# Logger.net
KiCad netlist of a schematic drawn in EAGLE
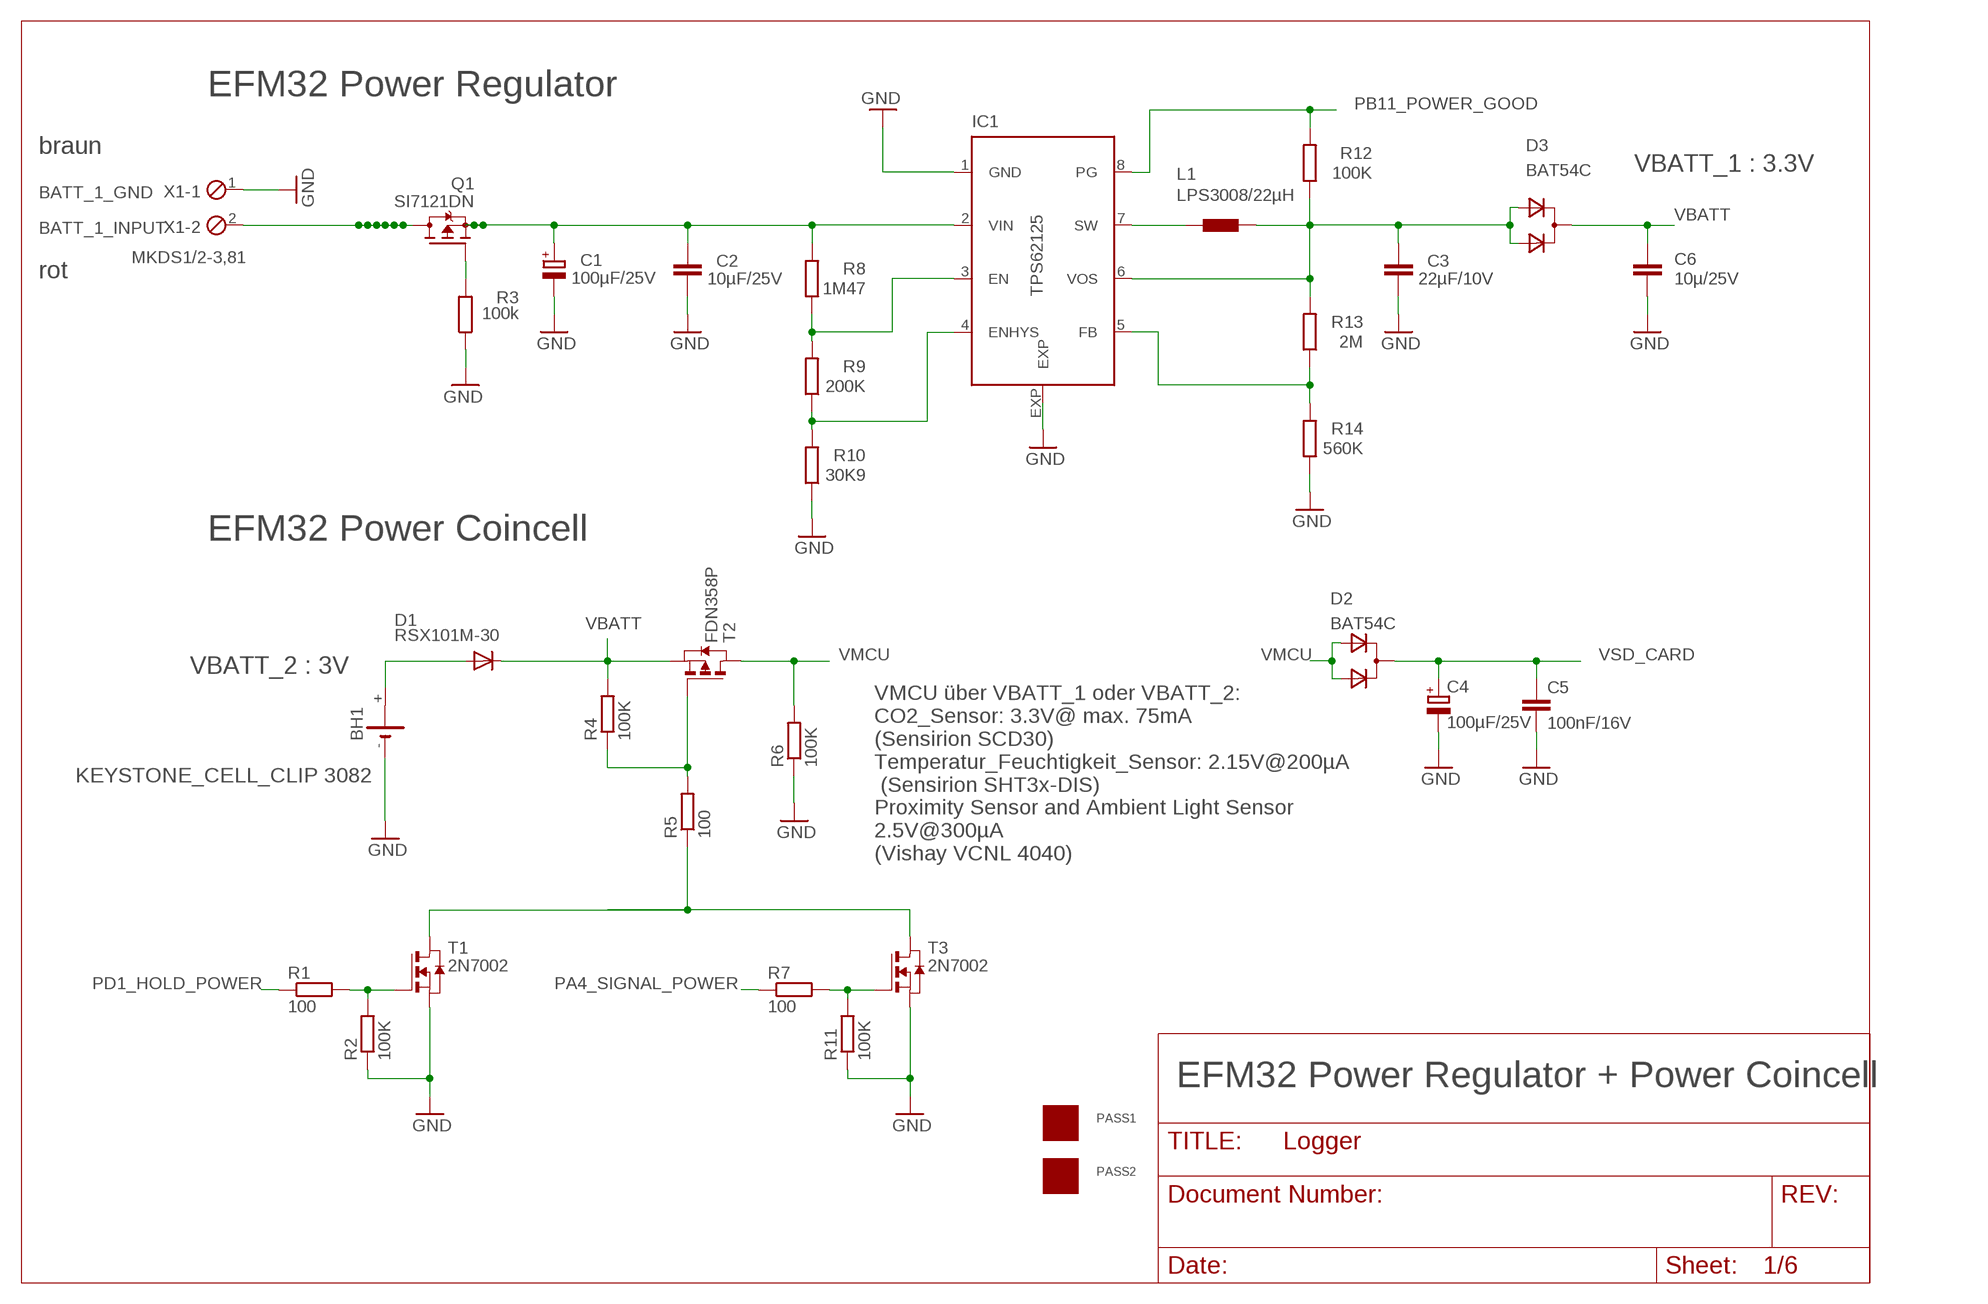
[diagram p0: schematic, sheet 1]
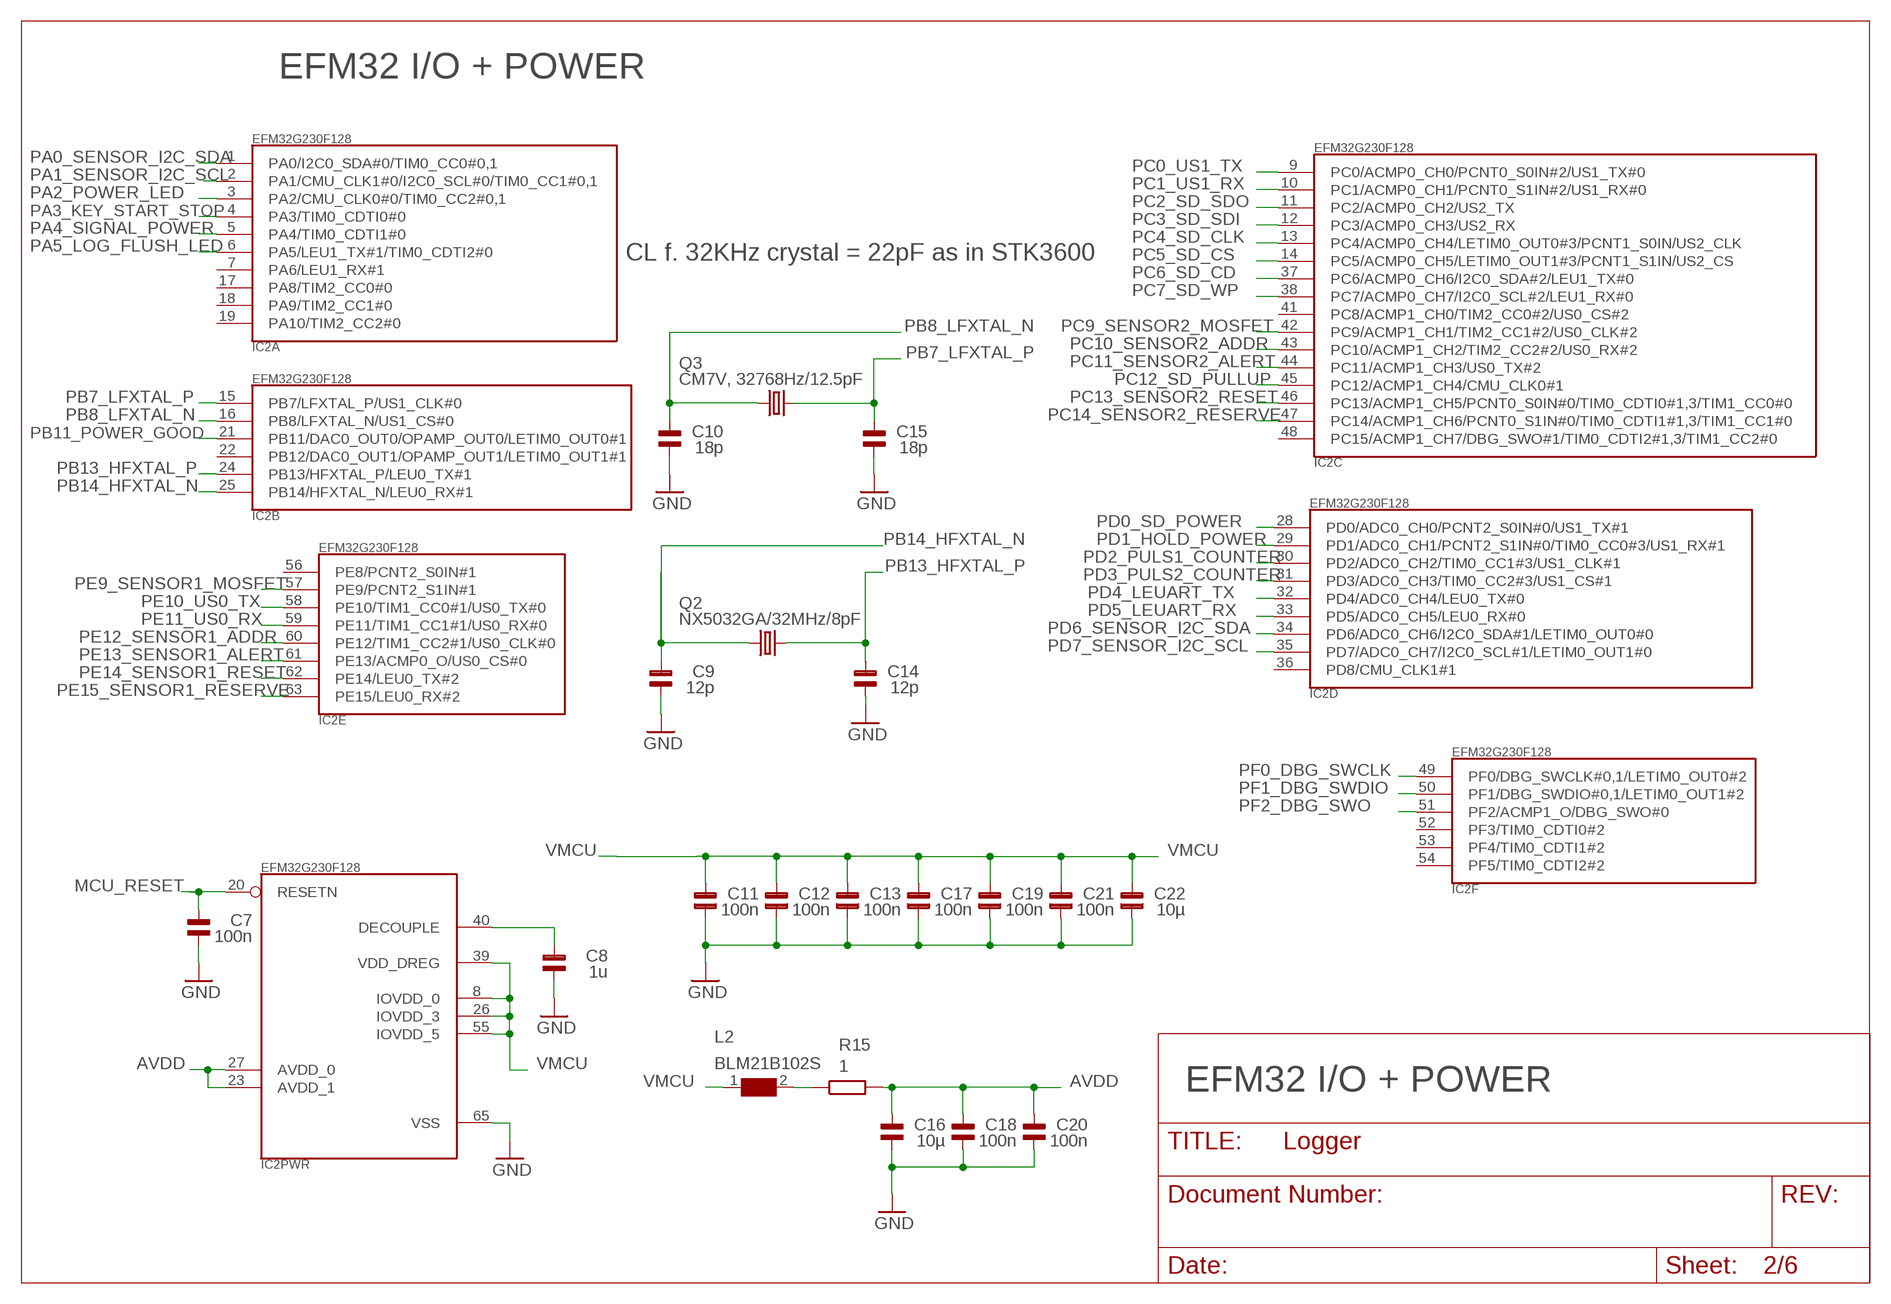
[diagram p1: schematic, sheet 2]
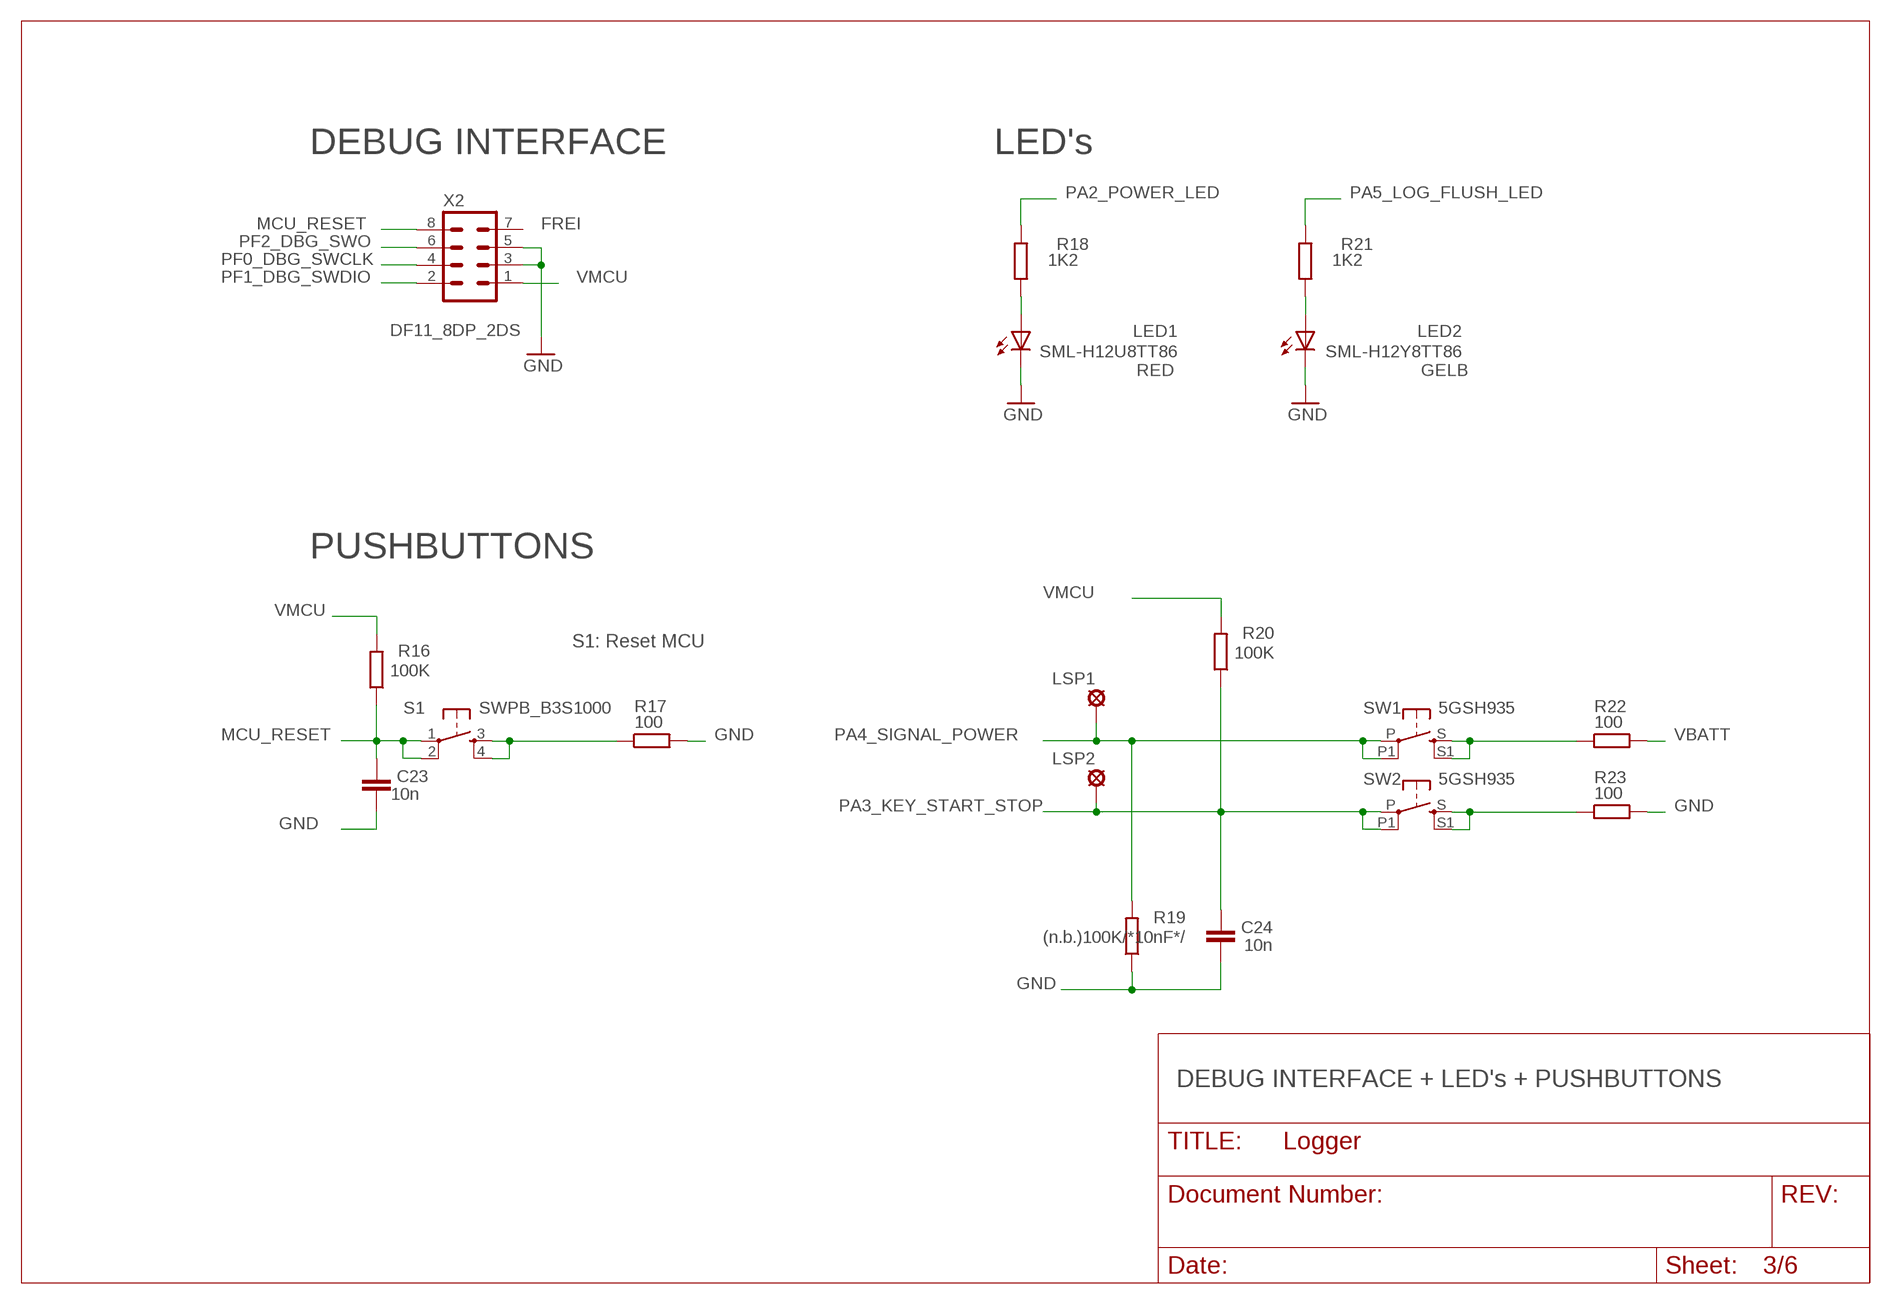
[diagram p2: schematic, sheet 3]
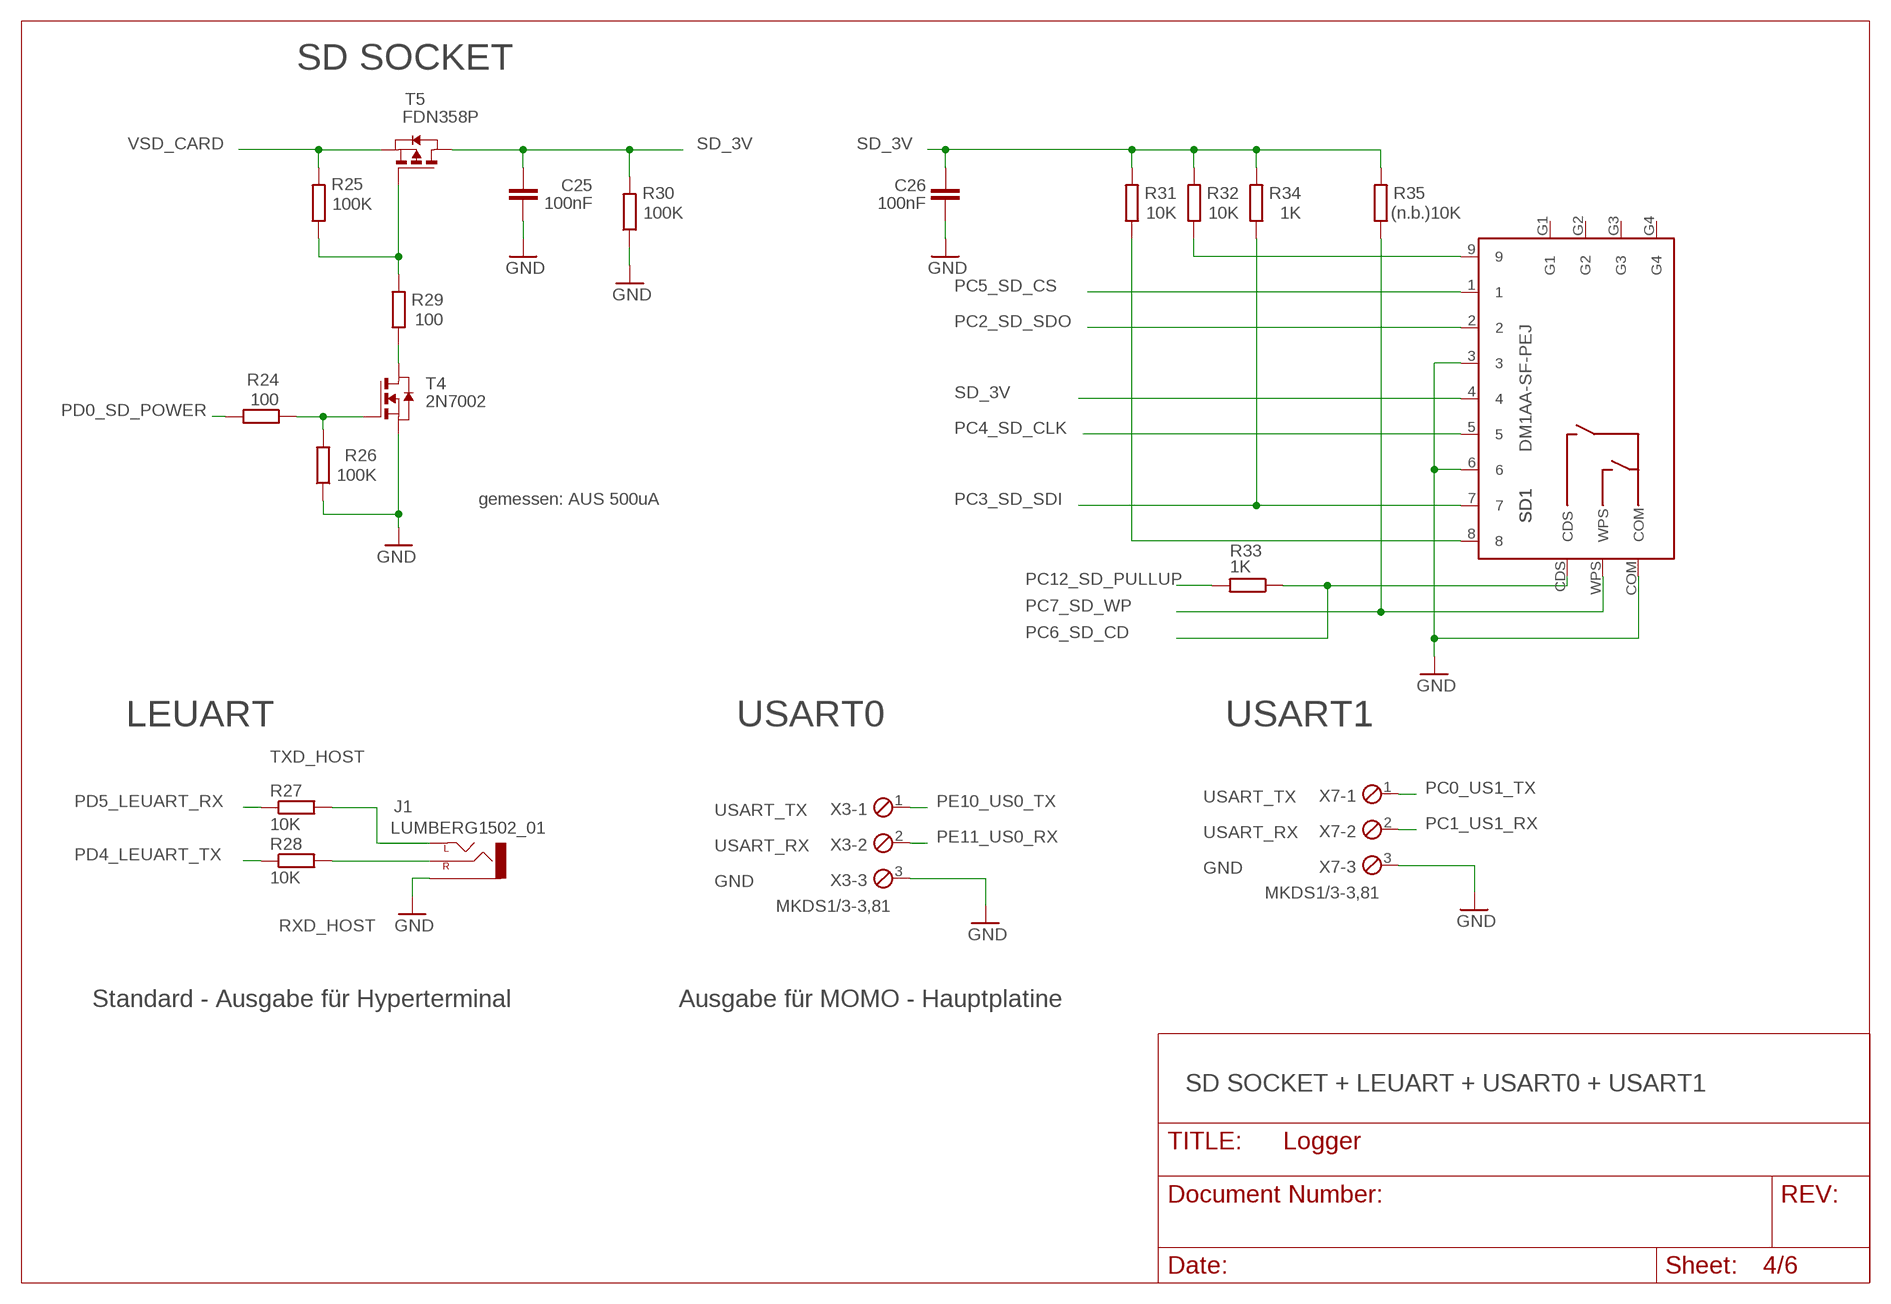
[diagram p3: schematic, sheet 4]
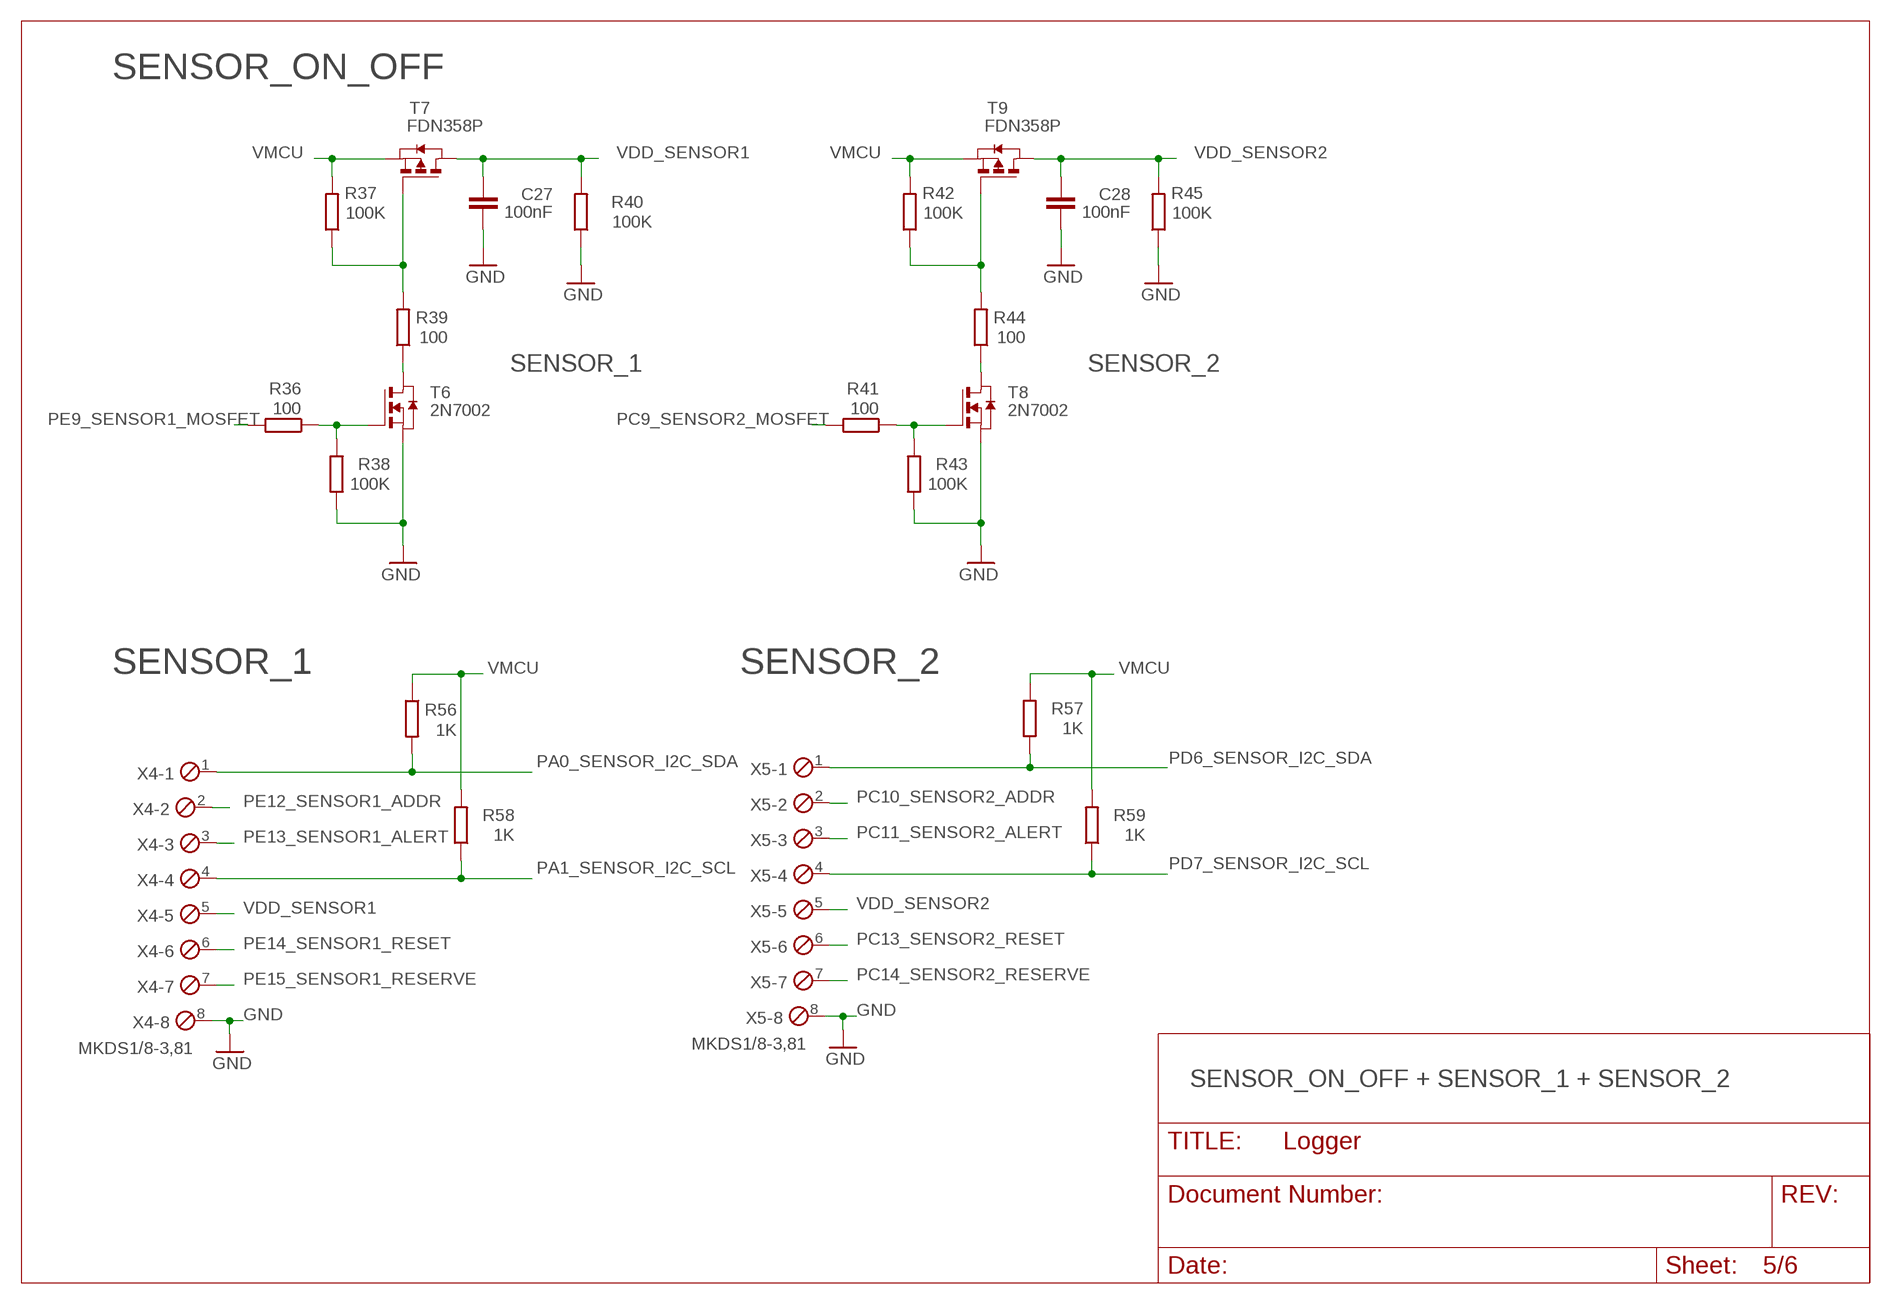
[diagram p4: schematic, sheet 5]
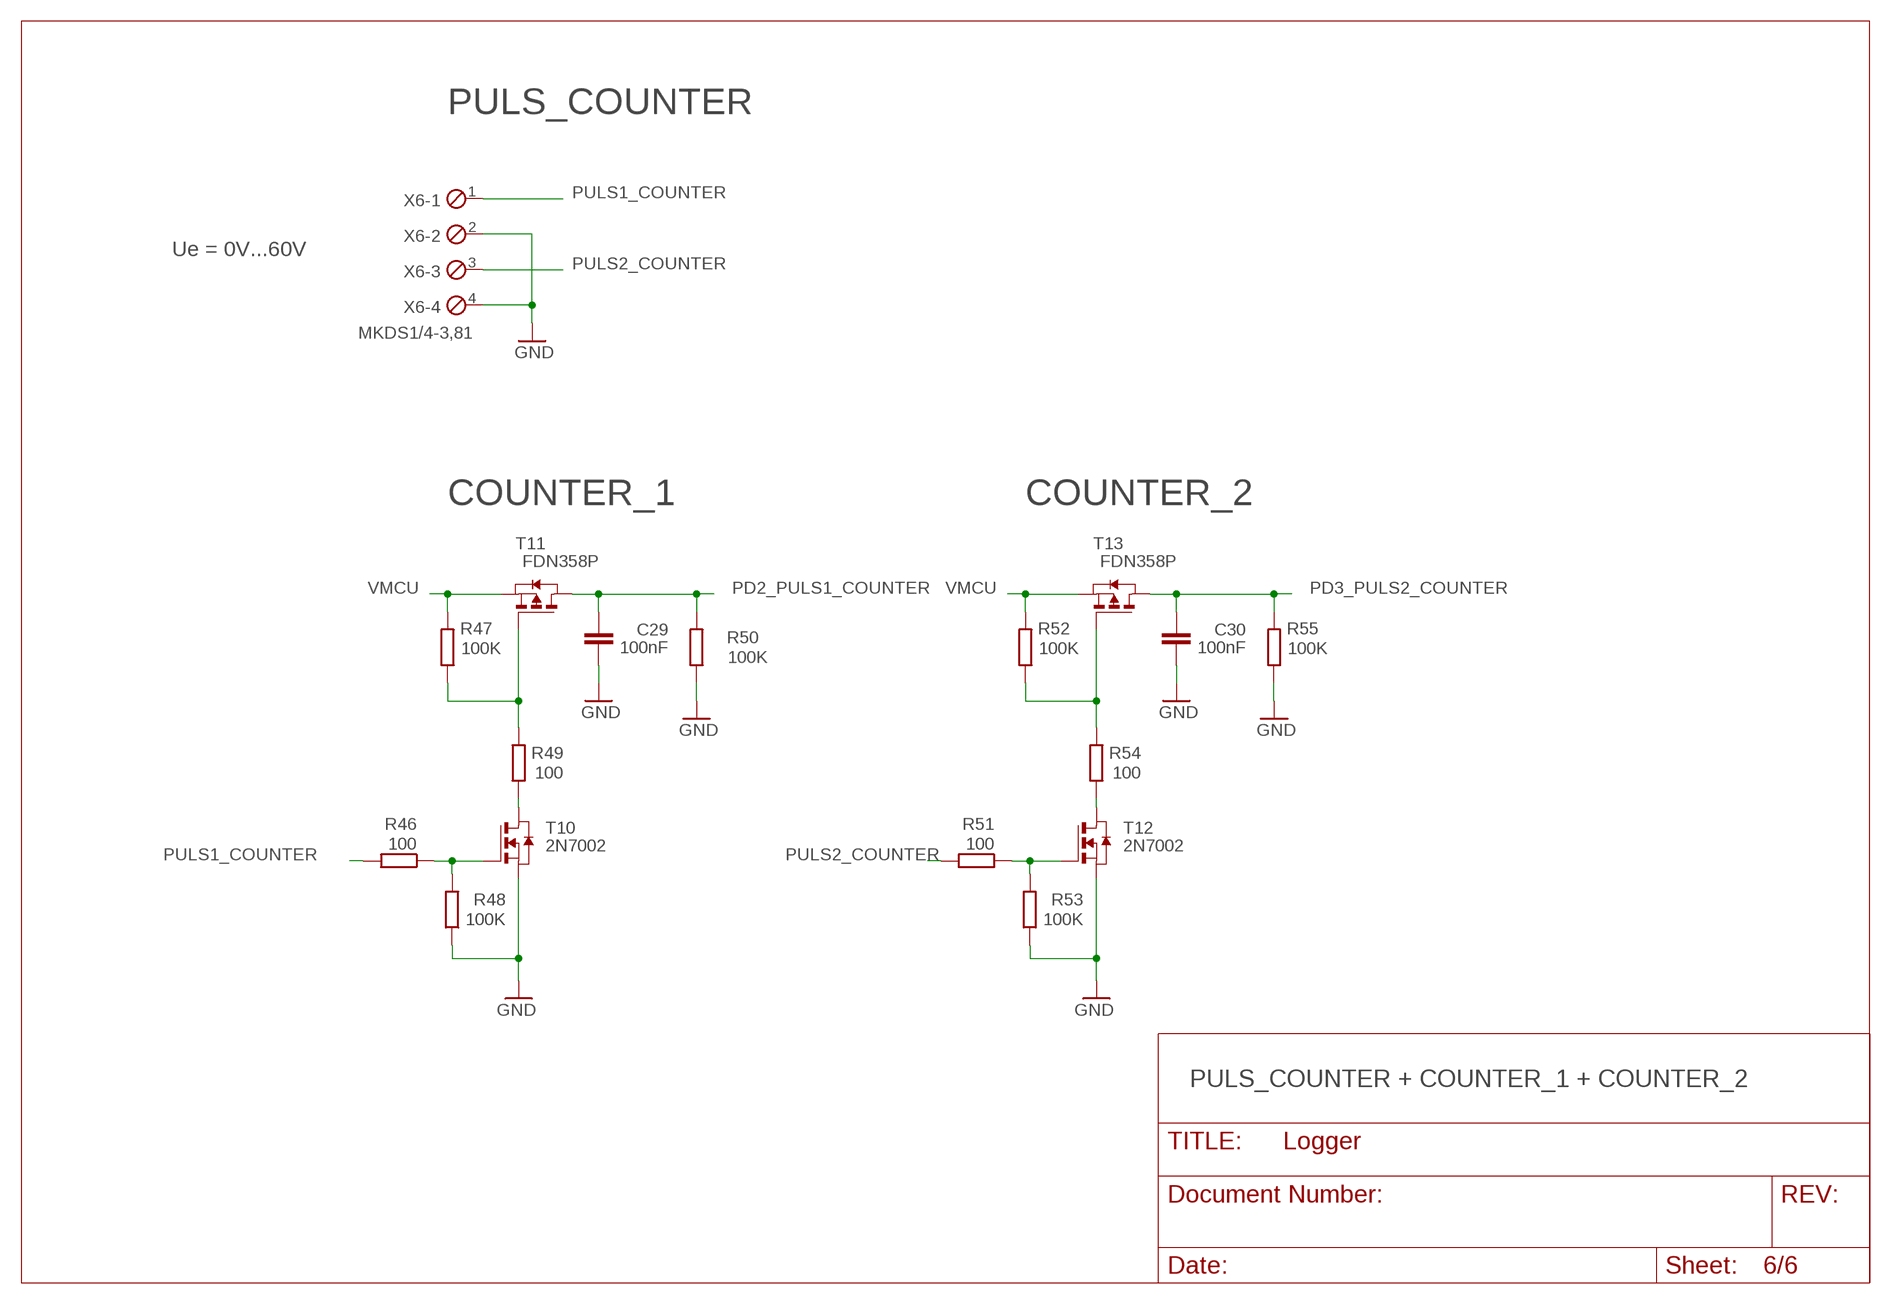
[diagram p5: schematic, sheet 6]

(export (version "E")
  (design (tool "Eeschema 10.0.6"))
  (components
    (comp (ref "C25")
      (value "100nF")
      (footprint "eagle-import:C0603")
      (libsource (lib "eagle-import") (part "resistor_C-EUC0603"))
    )
    (comp (ref "C26")
      (value "100nF")
      (footprint "eagle-import:C0603")
      (libsource (lib "eagle-import") (part "resistor_C-EUC0603"))
    )
    (comp (ref "J1")
      (value "LUMBERG1502_01")
      (footprint "eagle-import:LUMBERG1502_01")
      (libsource (lib "eagle-import") (part "LUMBERG1502_01"))
    )
    (comp (ref "R24")
      (value "100")
      (footprint "eagle-import:R0805")
      (libsource (lib "eagle-import") (part "resistor_R-EU_R0805"))
    )
    (comp (ref "R25")
      (value "100K")
      (footprint "eagle-import:R0805")
      (libsource (lib "eagle-import") (part "resistor_R-EU_R0805"))
    )
    (comp (ref "R26")
      (value "100K")
      (footprint "eagle-import:R0805")
      (libsource (lib "eagle-import") (part "resistor_R-EU_R0805"))
    )
    (comp (ref "R27")
      (value "10K")
      (footprint "eagle-import:R0805")
      (libsource (lib "eagle-import") (part "R-EU_R0805"))
    )
    (comp (ref "R28")
      (value "10K")
      (footprint "eagle-import:R0805")
      (libsource (lib "eagle-import") (part "R-EU_R0805"))
    )
    (comp (ref "R29")
      (value "100")
      (footprint "eagle-import:R0805")
      (libsource (lib "eagle-import") (part "resistor_R-EU_R0805"))
    )
    (comp (ref "R30")
      (value "100K")
      (footprint "eagle-import:R0805")
      (libsource (lib "eagle-import") (part "resistor_R-EU_R0805"))
    )
    (comp (ref "R31")
      (value "10K")
      (footprint "eagle-import:R0805")
      (libsource (lib "eagle-import") (part "resistor_R-EU_R0805"))
    )
    (comp (ref "R32")
      (value "10K")
      (footprint "eagle-import:R0805")
      (libsource (lib "eagle-import") (part "resistor_R-EU_R0805"))
    )
    (comp (ref "R33")
      (value "1K")
      (footprint "eagle-import:R0805")
      (libsource (lib "eagle-import") (part "resistor_R-EU_R0805"))
    )
    (comp (ref "R34")
      (value "1K")
      (footprint "eagle-import:R0805")
      (libsource (lib "eagle-import") (part "resistor_R-EU_R0805"))
    )
    (comp (ref "R35")
      (value "(n.b.)10K")
      (footprint "eagle-import:R0805")
      (libsource (lib "eagle-import") (part "resistor_R-EU_R0805"))
    )
    (comp (ref "SD1")
      (value "DM1AA-SF-PEJ")
      (footprint "eagle-import:DM1AA-SF-PEJ")
      (libsource (lib "eagle-import") (part "DM1AA-SF-PEJ"))
    )
    (comp (ref "T4")
      (value "2N7002")
      (footprint "eagle-import:ZETEX_SOT-23")
      (libsource (lib "eagle-import") (part "ZETEX_NMOSSOT23"))
    )
    (comp (ref "T5")
      (value "FDN358P")
      (footprint "eagle-import:ZETEX_SOT-23")
      (libsource (lib "eagle-import") (part "ZETEX_PMOSSOT23"))
    )
    (comp (ref "X3")
      (value "MKDS1/3-3,81")
      (footprint "eagle-import:3POL381")
      (libsource (lib "eagle-import") (part "MKDS1/3-3,81"))
    )
    (comp (ref "X7")
      (value "MKDS1/3-3,81")
      (footprint "eagle-import:3POL381")
      (libsource (lib "eagle-import") (part "MKDS1/3-3,81"))
    )
    (comp (ref "BH1")
      (value "KEYSTONE_CELL_CLIP 3082")
      (footprint "eagle-import:3082")
      (libsource (lib "eagle-import") (part "3082"))
    )
    (comp (ref "C1")
      (value "100µF/25V")
      (footprint "eagle-import:PANASONIC_E")
      (libsource (lib "eagle-import") (part "CPOL-EUE"))
    )
    (comp (ref "C2")
      (value "10µF/25V")
      (footprint "eagle-import:C1206")
      (libsource (lib "eagle-import") (part "C-EUC1206"))
    )
    (comp (ref "C3")
      (value "22µF/10V")
      (footprint "eagle-import:C0603")
      (libsource (lib "eagle-import") (part "C-EUC0603"))
    )
    (comp (ref "C4")
      (value "100µF/25V")
      (footprint "eagle-import:PANASONIC_E")
      (libsource (lib "eagle-import") (part "CPOL-EUE"))
    )
    (comp (ref "C5")
      (value "100nF/16V")
      (footprint "eagle-import:C0805")
      (libsource (lib "eagle-import") (part "C-EUC0805"))
    )
    (comp (ref "C6")
      (value "10µ/25V")
      (footprint "eagle-import:C1206")
      (libsource (lib "eagle-import") (part "C-EUC1206"))
    )
    (comp (ref "D1")
      (value "RSX101M-30")
      (footprint "eagle-import:SOD123")
      (libsource (lib "eagle-import") (part "DIODE-SOD123"))
    )
    (comp (ref "D2")
      (value "BAT54C")
      (footprint "eagle-import:SOT-23$1")
      (libsource (lib "eagle-import") (part "D2A_SOT23"))
    )
    (comp (ref "D3")
      (value "BAT54C")
      (footprint "eagle-import:SOT-23$1")
      (libsource (lib "eagle-import") (part "D2A_SOT23"))
    )
    (comp (ref "IC1")
      (value "TPS62125")
      (footprint "eagle-import:DSG_PWSO-N8_EXP")
      (libsource (lib "eagle-import") (part "TPS62125"))
    )
    (comp (ref "L1")
      (value "LPS3008/22µH")
      (footprint "eagle-import:LPS3008")
      (libsource (lib "eagle-import") (part "LPS3008"))
    )
    (comp (ref "PASS1")
      (value "ROUND_1MM1.5")
      (footprint "eagle-import:ROUND2_1.5MM")
      (libsource (lib "eagle-import") (part "ROUND_1MM1.5"))
    )
    (comp (ref "PASS2")
      (value "ROUND_1MM1.5")
      (footprint "eagle-import:ROUND2_1.5MM")
      (libsource (lib "eagle-import") (part "ROUND_1MM1.5"))
    )
    (comp (ref "Q1")
      (value "SI7121DN")
      (footprint "eagle-import:TRANSISTOR-FET_1212-8S")
      (libsource (lib "eagle-import") (part "TRANSISTOR-FET_SI7113DN"))
    )
    (comp (ref "R1")
      (value "100")
      (footprint "eagle-import:R0805")
      (libsource (lib "eagle-import") (part "R-EU_R0805"))
    )
    (comp (ref "R2")
      (value "100K")
      (footprint "eagle-import:R0805")
      (libsource (lib "eagle-import") (part "R-EU_R0805"))
    )
    (comp (ref "R3")
      (value "100k")
      (footprint "eagle-import:R0805")
      (libsource (lib "eagle-import") (part "resistor_R-EU_R0805"))
    )
    (comp (ref "R4")
      (value "100K")
      (footprint "eagle-import:R0805")
      (libsource (lib "eagle-import") (part "R-EU_R0805"))
    )
    (comp (ref "R5")
      (value "100")
      (footprint "eagle-import:R0805")
      (libsource (lib "eagle-import") (part "R-EU_R0805"))
    )
    (comp (ref "R6")
      (value "100K")
      (footprint "eagle-import:R0805")
      (libsource (lib "eagle-import") (part "R-EU_R0805"))
    )
    (comp (ref "R7")
      (value "100")
      (footprint "eagle-import:R0805")
      (libsource (lib "eagle-import") (part "R-EU_R0805"))
    )
    (comp (ref "R8")
      (value "1M47")
      (footprint "eagle-import:R0805")
      (libsource (lib "eagle-import") (part "R-EU_R0805"))
    )
    (comp (ref "R9")
      (value "200K")
      (footprint "eagle-import:R0805")
      (libsource (lib "eagle-import") (part "R-EU_R0805"))
    )
    (comp (ref "R10")
      (value "30K9")
      (footprint "eagle-import:R0805")
      (libsource (lib "eagle-import") (part "R-EU_R0805"))
    )
    (comp (ref "R11")
      (value "100K")
      (footprint "eagle-import:R0805")
      (libsource (lib "eagle-import") (part "R-EU_R0805"))
    )
    (comp (ref "R12")
      (value "100K")
      (footprint "eagle-import:R0805")
      (libsource (lib "eagle-import") (part "R-EU_R0805"))
    )
    (comp (ref "R13")
      (value "2M")
      (footprint "eagle-import:R0805")
      (libsource (lib "eagle-import") (part "R-EU_R0805"))
    )
    (comp (ref "R14")
      (value "560K")
      (footprint "eagle-import:R0805")
      (libsource (lib "eagle-import") (part "R-EU_R0805"))
    )
    (comp (ref "T1")
      (value "2N7002")
      (footprint "eagle-import:SOT-23")
      (fields (field (name "OC_FARNELL") "unknown") (field (name "OC_NEWARK") "unknown"))
      (libsource (lib "eagle-import") (part "NMOSSOT23"))
    )
    (comp (ref "T2")
      (value "FDN358P")
      (footprint "eagle-import:ZETEX_SOT-23")
      (libsource (lib "eagle-import") (part "ZETEX_PMOSSOT23"))
    )
    (comp (ref "T3")
      (value "2N7002")
      (footprint "eagle-import:SOT-23")
      (fields (field (name "OC_FARNELL") "unknown") (field (name "OC_NEWARK") "unknown"))
      (libsource (lib "eagle-import") (part "NMOSSOT23"))
    )
    (comp (ref "X1")
      (value "MKDS1/2-3,81")
      (footprint "eagle-import:2POL381")
      (libsource (lib "eagle-import") (part "MKDS1/2-3,81"))
    )
    (comp (ref "C23")
      (value "10n")
      (footprint "eagle-import:C0603")
      (libsource (lib "eagle-import") (part "resistor_C-EUC0603"))
    )
    (comp (ref "C24")
      (value "10n")
      (footprint "eagle-import:C0603K")
      (libsource (lib "eagle-import") (part "C-EUC0603K"))
    )
    (comp (ref "LED1")
      (value "SML-H12U8TT86")
      (footprint "eagle-import:CHIPLED_0805")
      (libsource (lib "eagle-import") (part "LEDCHIPLED_0805"))
    )
    (comp (ref "LED2")
      (value "SML-H12Y8TT86")
      (footprint "eagle-import:CHIPLED_0805")
      (libsource (lib "eagle-import") (part "LEDCHIPLED_0805"))
    )
    (comp (ref "LSP1")
      (value "(n.b.)SE13")
      (footprint "eagle-import:SE13")
      (libsource (lib "eagle-import") (part "SE13"))
    )
    (comp (ref "LSP2")
      (value "(n.b.)SE13")
      (footprint "eagle-import:SE13")
      (libsource (lib "eagle-import") (part "SE13"))
    )
    (comp (ref "R16")
      (value "100K")
      (footprint "eagle-import:R0805")
      (libsource (lib "eagle-import") (part "resistor_R-EU_R0805"))
    )
    (comp (ref "R17")
      (value "100")
      (footprint "eagle-import:R0805")
      (libsource (lib "eagle-import") (part "resistor_R-EU_R0805"))
    )
    (comp (ref "R18")
      (value "1K2")
      (footprint "eagle-import:R0805")
      (libsource (lib "eagle-import") (part "resistor_R-EU_R0805"))
    )
    (comp (ref "R19")
      (value "(n.b.)100K/*10nF*/")
      (footprint "eagle-import:R0805")
      (libsource (lib "eagle-import") (part "resistor_R-EU_R0805"))
    )
    (comp (ref "R20")
      (value "100K")
      (footprint "eagle-import:R0805")
      (libsource (lib "eagle-import") (part "resistor_R-EU_R0805"))
    )
    (comp (ref "R21")
      (value "1K2")
      (footprint "eagle-import:R0805")
      (libsource (lib "eagle-import") (part "resistor_R-EU_R0805"))
    )
    (comp (ref "R22")
      (value "100")
      (footprint "eagle-import:R0805")
      (libsource (lib "eagle-import") (part "resistor_R-EU_R0805"))
    )
    (comp (ref "R23")
      (value "100")
      (footprint "eagle-import:R0805")
      (libsource (lib "eagle-import") (part "resistor_R-EU_R0805"))
    )
    (comp (ref "S1")
      (value "SWPB_B3S1000")
      (footprint "eagle-import:DTSM-6")
      (libsource (lib "eagle-import") (part "DTSM-6"))
    )
    (comp (ref "SW1")
      (value "5GSH935")
      (footprint "eagle-import:MULTIMEC_5GSH935")
      (libsource (lib "eagle-import") (part "5GSH935"))
    )
    (comp (ref "SW2")
      (value "5GSH935")
      (footprint "eagle-import:MULTIMEC_5GSH935")
      (libsource (lib "eagle-import") (part "5GSH935"))
    )
    (comp (ref "X2")
      (value "DF11_8DP_2DS")
      (footprint "eagle-import:DP11_8DP-2DS")
      (libsource (lib "eagle-import") (part "DP11_8DP_2DS"))
    )
    (comp (ref "C29")
      (value "100nF")
      (footprint "eagle-import:C0603")
      (libsource (lib "eagle-import") (part "resistor_C-EUC0603"))
    )
    (comp (ref "C30")
      (value "100nF")
      (footprint "eagle-import:C0603")
      (libsource (lib "eagle-import") (part "resistor_C-EUC0603"))
    )
    (comp (ref "R46")
      (value "100")
      (footprint "eagle-import:R0805")
      (libsource (lib "eagle-import") (part "resistor_R-EU_R0805"))
    )
    (comp (ref "R47")
      (value "100K")
      (footprint "eagle-import:R0805")
      (libsource (lib "eagle-import") (part "resistor_R-EU_R0805"))
    )
    (comp (ref "R48")
      (value "100K")
      (footprint "eagle-import:R0805")
      (libsource (lib "eagle-import") (part "resistor_R-EU_R0805"))
    )
    (comp (ref "R49")
      (value "100")
      (footprint "eagle-import:R0805")
      (libsource (lib "eagle-import") (part "resistor_R-EU_R0805"))
    )
    (comp (ref "R50")
      (value "100K")
      (footprint "eagle-import:R0805")
      (libsource (lib "eagle-import") (part "resistor_R-EU_R0805"))
    )
    (comp (ref "R51")
      (value "100")
      (footprint "eagle-import:R0805")
      (libsource (lib "eagle-import") (part "resistor_R-EU_R0805"))
    )
    (comp (ref "R52")
      (value "100K")
      (footprint "eagle-import:R0805")
      (libsource (lib "eagle-import") (part "resistor_R-EU_R0805"))
    )
    (comp (ref "R53")
      (value "100K")
      (footprint "eagle-import:R0805")
      (libsource (lib "eagle-import") (part "resistor_R-EU_R0805"))
    )
    (comp (ref "R54")
      (value "100")
      (footprint "eagle-import:R0805")
      (libsource (lib "eagle-import") (part "resistor_R-EU_R0805"))
    )
    (comp (ref "R55")
      (value "100K")
      (footprint "eagle-import:R0805")
      (libsource (lib "eagle-import") (part "resistor_R-EU_R0805"))
    )
    (comp (ref "T10")
      (value "2N7002")
      (footprint "eagle-import:ZETEX_SOT-23")
      (libsource (lib "eagle-import") (part "ZETEX_NMOSSOT23"))
    )
    (comp (ref "T11")
      (value "FDN358P")
      (footprint "eagle-import:ZETEX_SOT-23")
      (libsource (lib "eagle-import") (part "ZETEX_PMOSSOT23"))
    )
    (comp (ref "T12")
      (value "2N7002")
      (footprint "eagle-import:ZETEX_SOT-23")
      (libsource (lib "eagle-import") (part "ZETEX_NMOSSOT23"))
    )
    (comp (ref "T13")
      (value "FDN358P")
      (footprint "eagle-import:ZETEX_SOT-23")
      (libsource (lib "eagle-import") (part "ZETEX_PMOSSOT23"))
    )
    (comp (ref "X6")
      (value "MKDS1/4-3,81")
      (footprint "eagle-import:4POL381")
      (libsource (lib "eagle-import") (part "MKDS1/4-3,81"))
    )
    (comp (ref "C7")
      (value "100n")
      (footprint "eagle-import:0805")
      (libsource (lib "eagle-import") (part "C_SMD0805"))
    )
    (comp (ref "C8")
      (value "1u")
      (footprint "eagle-import:0805")
      (libsource (lib "eagle-import") (part "C_SMD0805"))
    )
    (comp (ref "C9")
      (value "12p")
      (footprint "eagle-import:0805")
      (libsource (lib "eagle-import") (part "C_SMD0805"))
    )
    (comp (ref "C10")
      (value "18p")
      (footprint "eagle-import:0805")
      (libsource (lib "eagle-import") (part "C_SMD0805"))
    )
    (comp (ref "C11")
      (value "100n")
      (footprint "eagle-import:0805")
      (libsource (lib "eagle-import") (part "C_SMD0805"))
    )
    (comp (ref "C12")
      (value "100n")
      (footprint "eagle-import:0805")
      (libsource (lib "eagle-import") (part "C_SMD0805"))
    )
    (comp (ref "C13")
      (value "100n")
      (footprint "eagle-import:0805")
      (libsource (lib "eagle-import") (part "C_SMD0805"))
    )
    (comp (ref "C14")
      (value "12p")
      (footprint "eagle-import:0805")
      (libsource (lib "eagle-import") (part "C_SMD0805"))
    )
    (comp (ref "C15")
      (value "18p")
      (footprint "eagle-import:0805")
      (libsource (lib "eagle-import") (part "C_SMD0805"))
    )
    (comp (ref "C16")
      (value "10µ")
      (footprint "eagle-import:0805")
      (libsource (lib "eagle-import") (part "C_SMD0805"))
    )
    (comp (ref "C17")
      (value "100n")
      (footprint "eagle-import:0805")
      (libsource (lib "eagle-import") (part "C_SMD0805"))
    )
    (comp (ref "C18")
      (value "100n")
      (footprint "eagle-import:0805")
      (libsource (lib "eagle-import") (part "C_SMD0805"))
    )
    (comp (ref "C19")
      (value "100n")
      (footprint "eagle-import:0805")
      (libsource (lib "eagle-import") (part "C_SMD0805"))
    )
    (comp (ref "C20")
      (value "100n")
      (footprint "eagle-import:0805")
      (libsource (lib "eagle-import") (part "C_SMD0805"))
    )
    (comp (ref "C21")
      (value "100n")
      (footprint "eagle-import:0805")
      (libsource (lib "eagle-import") (part "C_SMD0805"))
    )
    (comp (ref "C22")
      (value "10µ")
      (footprint "eagle-import:0805")
      (libsource (lib "eagle-import") (part "C_SMD0805"))
    )
    (comp (ref "IC2")
      (value "EFM32G230F128")
      (footprint "eagle-import:QFN64")
      (libsource (lib "eagle-import") (part "EFM32G230F128"))
    )
    (comp (ref "L2")
      (value "BLM21B102S")
      (footprint "eagle-import:0805")
      (fields (field (name "MPN") "7427920"))
      (libsource (lib "eagle-import") (part "WE-CBF_0805-7427920"))
    )
    (comp (ref "Q2")
      (value "NX5032GA/32MHz/8pF")
      (footprint "eagle-import:CRYSTAL2P5.0X3.2")
      (libsource (lib "eagle-import") (part "CRYSTAL2P5.0X3.2"))
    )
    (comp (ref "Q3")
      (value "CM7V, 32768Hz/12.5pF")
      (footprint "eagle-import:CRYSTAL2P3.2X1.5")
      (libsource (lib "eagle-import") (part "CRYSTAL2P"))
    )
    (comp (ref "R15")
      (value "1")
      (footprint "eagle-import:R0805")
      (libsource (lib "eagle-import") (part "R-EU_R0805"))
    )
    (comp (ref "C27")
      (value "100nF")
      (footprint "eagle-import:C0603")
      (libsource (lib "eagle-import") (part "resistor_C-EUC0603"))
    )
    (comp (ref "C28")
      (value "100nF")
      (footprint "eagle-import:C0603")
      (libsource (lib "eagle-import") (part "resistor_C-EUC0603"))
    )
    (comp (ref "R36")
      (value "100")
      (footprint "eagle-import:R0805")
      (libsource (lib "eagle-import") (part "resistor_R-EU_R0805"))
    )
    (comp (ref "R37")
      (value "100K")
      (footprint "eagle-import:R0805")
      (libsource (lib "eagle-import") (part "resistor_R-EU_R0805"))
    )
    (comp (ref "R38")
      (value "100K")
      (footprint "eagle-import:R0805")
      (libsource (lib "eagle-import") (part "resistor_R-EU_R0805"))
    )
    (comp (ref "R39")
      (value "100")
      (footprint "eagle-import:R0805")
      (libsource (lib "eagle-import") (part "resistor_R-EU_R0805"))
    )
    (comp (ref "R40")
      (value "100K")
      (footprint "eagle-import:R0805")
      (libsource (lib "eagle-import") (part "resistor_R-EU_R0805"))
    )
    (comp (ref "R41")
      (value "100")
      (footprint "eagle-import:R0805")
      (libsource (lib "eagle-import") (part "resistor_R-EU_R0805"))
    )
    (comp (ref "R42")
      (value "100K")
      (footprint "eagle-import:R0805")
      (libsource (lib "eagle-import") (part "resistor_R-EU_R0805"))
    )
    (comp (ref "R43")
      (value "100K")
      (footprint "eagle-import:R0805")
      (libsource (lib "eagle-import") (part "resistor_R-EU_R0805"))
    )
    (comp (ref "R44")
      (value "100")
      (footprint "eagle-import:R0805")
      (libsource (lib "eagle-import") (part "resistor_R-EU_R0805"))
    )
    (comp (ref "R45")
      (value "100K")
      (footprint "eagle-import:R0805")
      (libsource (lib "eagle-import") (part "resistor_R-EU_R0805"))
    )
    (comp (ref "R56")
      (value "1K")
      (footprint "eagle-import:R0805")
      (libsource (lib "eagle-import") (part "resistor_R-EU_R0805"))
    )
    (comp (ref "R57")
      (value "1K")
      (footprint "eagle-import:R0805")
      (libsource (lib "eagle-import") (part "resistor_R-EU_R0805"))
    )
    (comp (ref "R58")
      (value "1K")
      (footprint "eagle-import:R0805")
      (libsource (lib "eagle-import") (part "resistor_R-EU_R0805"))
    )
    (comp (ref "R59")
      (value "1K")
      (footprint "eagle-import:R0805")
      (libsource (lib "eagle-import") (part "resistor_R-EU_R0805"))
    )
    (comp (ref "T6")
      (value "2N7002")
      (footprint "eagle-import:ZETEX_SOT-23")
      (libsource (lib "eagle-import") (part "ZETEX_NMOSSOT23"))
    )
    (comp (ref "T7")
      (value "FDN358P")
      (footprint "eagle-import:ZETEX_SOT-23")
      (libsource (lib "eagle-import") (part "ZETEX_PMOSSOT23"))
    )
    (comp (ref "T8")
      (value "2N7002")
      (footprint "eagle-import:ZETEX_SOT-23")
      (libsource (lib "eagle-import") (part "ZETEX_NMOSSOT23"))
    )
    (comp (ref "T9")
      (value "FDN358P")
      (footprint "eagle-import:ZETEX_SOT-23")
      (libsource (lib "eagle-import") (part "ZETEX_PMOSSOT23"))
    )
    (comp (ref "X4")
      (value "MKDS1/8-3,81")
      (footprint "eagle-import:8POL381")
      (libsource (lib "eagle-import") (part "MKDS1/8-3,81"))
    )
    (comp (ref "X5")
      (value "MKDS1/8-3,81")
      (footprint "eagle-import:8POL381")
      (libsource (lib "eagle-import") (part "MKDS1/8-3,81"))
    )
  )
  (nets
    (net (code "1") (name "AVDD") (class "Default")
      (node (ref "C16") (pin "2") (pinfunction "2_2") (pintype "passive"))
      (node (ref "C18") (pin "2") (pinfunction "2_2") (pintype "passive"))
      (node (ref "C20") (pin "2") (pinfunction "2_2") (pintype "passive"))
      (node (ref "IC2") (pin "23") (pinfunction "AVDD_1_23") (pintype "power_in"))
      (node (ref "IC2") (pin "27") (pinfunction "AVDD_0_27") (pintype "power_in"))
      (node (ref "R15") (pin "2") (pinfunction "2_2") (pintype "passive"))
    )
    (net (code "2") (name "GND") (class "Default")
      (node (ref "BH1") (pin "-") (pinfunction "-_-") (pintype "passive"))
      (node (ref "C1") (pin "-") (pinfunction "-_-") (pintype "passive"))
      (node (ref "C10") (pin "1") (pinfunction "1_1") (pintype "passive"))
      (node (ref "C11") (pin "1") (pinfunction "1_1") (pintype "passive"))
      (node (ref "C12") (pin "1") (pinfunction "1_1") (pintype "passive"))
      (node (ref "C13") (pin "1") (pinfunction "1_1") (pintype "passive"))
      (node (ref "C14") (pin "1") (pinfunction "1_1") (pintype "passive"))
      (node (ref "C15") (pin "1") (pinfunction "1_1") (pintype "passive"))
      (node (ref "C16") (pin "1") (pinfunction "1_1") (pintype "passive"))
      (node (ref "C17") (pin "1") (pinfunction "1_1") (pintype "passive"))
      (node (ref "C18") (pin "1") (pinfunction "1_1") (pintype "passive"))
      (node (ref "C19") (pin "1") (pinfunction "1_1") (pintype "passive"))
      (node (ref "C2") (pin "2") (pinfunction "2_2") (pintype "passive"))
      (node (ref "C20") (pin "1") (pinfunction "1_1") (pintype "passive"))
      (node (ref "C21") (pin "1") (pinfunction "1_1") (pintype "passive"))
      (node (ref "C22") (pin "1") (pinfunction "1_1") (pintype "passive"))
      (node (ref "C23") (pin "1") (pinfunction "1_1") (pintype "passive"))
      (node (ref "C24") (pin "1") (pinfunction "1_1") (pintype "passive"))
      (node (ref "C25") (pin "2") (pinfunction "2_2") (pintype "passive"))
      (node (ref "C26") (pin "2") (pinfunction "2_2") (pintype "passive"))
      (node (ref "C27") (pin "2") (pinfunction "2_2") (pintype "passive"))
      (node (ref "C28") (pin "2") (pinfunction "2_2") (pintype "passive"))
      (node (ref "C29") (pin "2") (pinfunction "2_2") (pintype "passive"))
      (node (ref "C3") (pin "2") (pinfunction "2_2") (pintype "passive"))
      (node (ref "C30") (pin "2") (pinfunction "2_2") (pintype "passive"))
      (node (ref "C4") (pin "-") (pinfunction "-_-") (pintype "passive"))
      (node (ref "C5") (pin "2") (pinfunction "2_2") (pintype "passive"))
      (node (ref "C6") (pin "1") (pinfunction "1_1") (pintype "passive"))
      (node (ref "C7") (pin "1") (pinfunction "1_1") (pintype "passive"))
      (node (ref "C8") (pin "1") (pinfunction "1_1") (pintype "passive"))
      (node (ref "C9") (pin "1") (pinfunction "1_1") (pintype "passive"))
      (node (ref "IC1") (pin "1") (pinfunction "GND_1") (pintype "passive"))
      (node (ref "IC1") (pin "EXP") (pinfunction "EXP_EXP") (pintype "passive"))
      (node (ref "IC2") (pin "65") (pinfunction "VSS_65") (pintype "power_in"))
      (node (ref "J1") (pin "P$1") (pinfunction "1-SLEEVE_P$1") (pintype "bidirectional"))
      (node (ref "LED1") (pin "C") (pinfunction "C_C") (pintype "passive"))
      (node (ref "LED2") (pin "C") (pinfunction "C_C") (pintype "passive"))
      (node (ref "R10") (pin "1") (pinfunction "1_1") (pintype "passive"))
      (node (ref "R11") (pin "1") (pinfunction "1_1") (pintype "passive"))
      (node (ref "R14") (pin "1") (pinfunction "1_1") (pintype "passive"))
      (node (ref "R17") (pin "2") (pinfunction "2_2") (pintype "passive"))
      (node (ref "R19") (pin "1") (pinfunction "1_1") (pintype "passive"))
      (node (ref "R2") (pin "1") (pinfunction "1_1") (pintype "passive"))
      (node (ref "R23") (pin "2") (pinfunction "2_2") (pintype "passive"))
      (node (ref "R26") (pin "1") (pinfunction "1_1") (pintype "passive"))
      (node (ref "R3") (pin "1") (pinfunction "1_1") (pintype "passive"))
      (node (ref "R30") (pin "1") (pinfunction "1_1") (pintype "passive"))
      (node (ref "R38") (pin "1") (pinfunction "1_1") (pintype "passive"))
      (node (ref "R40") (pin "1") (pinfunction "1_1") (pintype "passive"))
      (node (ref "R43") (pin "1") (pinfunction "1_1") (pintype "passive"))
      (node (ref "R45") (pin "1") (pinfunction "1_1") (pintype "passive"))
      (node (ref "R48") (pin "1") (pinfunction "1_1") (pintype "passive"))
      (node (ref "R50") (pin "1") (pinfunction "1_1") (pintype "passive"))
      (node (ref "R53") (pin "1") (pinfunction "1_1") (pintype "passive"))
      (node (ref "R55") (pin "1") (pinfunction "1_1") (pintype "passive"))
      (node (ref "R6") (pin "1") (pinfunction "1_1") (pintype "passive"))
      (node (ref "SD1") (pin "3") (pinfunction "3_3") (pintype "bidirectional"))
      (node (ref "SD1") (pin "6") (pinfunction "6_6") (pintype "bidirectional"))
      (node (ref "SD1") (pin "COM") (pinfunction "COM_COM") (pintype "passive"))
      (node (ref "T1") (pin "2") (pinfunction "S_2") (pintype "passive"))
      (node (ref "T10") (pin "2") (pinfunction "S_2") (pintype "passive"))
      (node (ref "T12") (pin "2") (pinfunction "S_2") (pintype "passive"))
      (node (ref "T3") (pin "2") (pinfunction "S_2") (pintype "passive"))
      (node (ref "T4") (pin "2") (pinfunction "S_2") (pintype "passive"))
      (node (ref "T6") (pin "2") (pinfunction "S_2") (pintype "passive"))
      (node (ref "T8") (pin "2") (pinfunction "S_2") (pintype "passive"))
      (node (ref "X1") (pin "1") (pinfunction "1_1") (pintype "passive"))
      (node (ref "X2") (pin "3") (pinfunction "3_3") (pintype "passive"))
      (node (ref "X2") (pin "5") (pinfunction "5_5") (pintype "passive"))
      (node (ref "X3") (pin "3") (pinfunction "1_3") (pintype "passive"))
      (node (ref "X4") (pin "8") (pinfunction "1_8") (pintype "passive"))
      (node (ref "X5") (pin "8") (pinfunction "1_8") (pintype "passive"))
      (node (ref "X6") (pin "2") (pinfunction "1_2") (pintype "passive"))
      (node (ref "X6") (pin "4") (pinfunction "1_4") (pintype "passive"))
      (node (ref "X7") (pin "3") (pinfunction "1_3") (pintype "passive"))
    )
    (net (code "3") (name "MCU_RESET") (class "Default")
      (node (ref "C23") (pin "2") (pinfunction "2_2") (pintype "passive"))
      (node (ref "C7") (pin "2") (pinfunction "2_2") (pintype "passive"))
      (node (ref "IC2") (pin "20") (pinfunction "RESETN_20") (pintype "passive"))
      (node (ref "R16") (pin "1") (pinfunction "1_1") (pintype "passive"))
      (node (ref "S1") (pin "1") (pinfunction "1_1") (pintype "passive"))
      (node (ref "S1") (pin "2") (pinfunction "2_2") (pintype "passive"))
      (node (ref "X2") (pin "8") (pinfunction "8_8") (pintype "passive"))
    )
    (net (code "4") (name "Net-(BH1-Pad+)") (class "Default")
      (node (ref "BH1") (pin "+") (pinfunction "+_+") (pintype "passive"))
      (node (ref "D1") (pin "A") (pinfunction "A_A") (pintype "passive"))
    )
    (net (code "5") (name "Net-(D3-A1)") (class "Default")
      (node (ref "C3") (pin "1") (pinfunction "1_1") (pintype "passive"))
      (node (ref "D3") (pin "2") (pinfunction "A1_2") (pintype "passive"))
      (node (ref "D3") (pin "3") (pinfunction "A2_3") (pintype "passive"))
      (node (ref "IC1") (pin "6") (pinfunction "VOS_6") (pintype "input"))
      (node (ref "L1") (pin "2") (pinfunction "2_2") (pintype "passive"))
      (node (ref "R12") (pin "1") (pinfunction "1_1") (pintype "passive"))
      (node (ref "R13") (pin "2") (pinfunction "2_2") (pintype "passive"))
    )
    (net (code "6") (name "Net-(IC1-EN)") (class "Default")
      (node (ref "IC1") (pin "3") (pinfunction "EN_3") (pintype "input"))
      (node (ref "R8") (pin "1") (pinfunction "1_1") (pintype "passive"))
      (node (ref "R9") (pin "2") (pinfunction "2_2") (pintype "passive"))
    )
    (net (code "7") (name "Net-(IC1-ENHYS)") (class "Default")
      (node (ref "IC1") (pin "4") (pinfunction "ENHYS_4") (pintype "output"))
      (node (ref "R10") (pin "2") (pinfunction "2_2") (pintype "passive"))
      (node (ref "R9") (pin "1") (pinfunction "1_1") (pintype "passive"))
    )
    (net (code "8") (name "Net-(IC1-FB)") (class "Default")
      (node (ref "IC1") (pin "5") (pinfunction "FB_5") (pintype "input"))
      (node (ref "R13") (pin "1") (pinfunction "1_1") (pintype "passive"))
      (node (ref "R14") (pin "2") (pinfunction "2_2") (pintype "passive"))
    )
    (net (code "9") (name "Net-(IC1-SW)") (class "Default")
      (node (ref "IC1") (pin "7") (pinfunction "SW_7") (pintype "output"))
      (node (ref "L1") (pin "1") (pinfunction "1_1") (pintype "passive"))
    )
    (net (code "10") (name "Net-(IC1-VIN)") (class "Default")
      (node (ref "C1") (pin "+") (pinfunction "+_+") (pintype "passive"))
      (node (ref "C2") (pin "1") (pinfunction "1_1") (pintype "passive"))
      (node (ref "IC1") (pin "2") (pinfunction "VIN_2") (pintype "passive"))
      (node (ref "Q1") (pin "1") (pinfunction "S_1") (pintype "passive"))
      (node (ref "Q1") (pin "2") (pinfunction "S_2") (pintype "passive"))
      (node (ref "Q1") (pin "3") (pinfunction "S_3") (pintype "passive"))
      (node (ref "R8") (pin "2") (pinfunction "2_2") (pintype "passive"))
    )
    (net (code "11") (name "Net-(IC2G-DECOUPLE)") (class "Default")
      (node (ref "C8") (pin "2") (pinfunction "2_2") (pintype "passive"))
      (node (ref "IC2") (pin "40") (pinfunction "DECOUPLE_40") (pintype "power_in"))
    )
    (net (code "12") (name "Net-(L2-Pad2)") (class "Default")
      (node (ref "L2") (pin "2") (pinfunction "2_2") (pintype "passive"))
      (node (ref "R15") (pin "1") (pinfunction "1_1") (pintype "passive"))
    )
    (net (code "13") (name "Net-(LED1-PadA)") (class "Default")
      (node (ref "LED1") (pin "A") (pinfunction "A_A") (pintype "passive"))
      (node (ref "R18") (pin "2") (pinfunction "2_2") (pintype "passive"))
    )
    (net (code "14") (name "Net-(LED2-PadA)") (class "Default")
      (node (ref "LED2") (pin "A") (pinfunction "A_A") (pintype "passive"))
      (node (ref "R21") (pin "2") (pinfunction "2_2") (pintype "passive"))
    )
    (net (code "15") (name "Net-(Q1-G)") (class "Default")
      (node (ref "Q1") (pin "4") (pinfunction "G_4") (pintype "passive"))
      (node (ref "R3") (pin "2") (pinfunction "2_2") (pintype "passive"))
    )
    (net (code "16") (name "Net-(R17-Pad1)") (class "Default")
      (node (ref "R17") (pin "1") (pinfunction "1_1") (pintype "passive"))
      (node (ref "S1") (pin "3") (pinfunction "3_3") (pintype "passive"))
      (node (ref "S1") (pin "4") (pinfunction "4_4") (pintype "passive"))
    )
    (net (code "17") (name "Net-(R22-Pad1)") (class "Default")
      (node (ref "R22") (pin "1") (pinfunction "1_1") (pintype "passive"))
      (node (ref "SW1") (pin "S") (pinfunction "S_S") (pintype "passive"))
      (node (ref "SW1") (pin "S1") (pinfunction "S1_S1") (pintype "passive"))
    )
    (net (code "18") (name "Net-(R23-Pad1)") (class "Default")
      (node (ref "R23") (pin "1") (pinfunction "1_1") (pintype "passive"))
      (node (ref "SW2") (pin "S") (pinfunction "S_S") (pintype "passive"))
      (node (ref "SW2") (pin "S1") (pinfunction "S1_S1") (pintype "passive"))
    )
    (net (code "19") (name "Net-(R31-Pad1)") (class "Default")
      (node (ref "R31") (pin "1") (pinfunction "1_1") (pintype "passive"))
      (node (ref "SD1") (pin "8") (pinfunction "8_8") (pintype "bidirectional"))
    )
    (net (code "20") (name "Net-(R32-Pad1)") (class "Default")
      (node (ref "R32") (pin "1") (pinfunction "1_1") (pintype "passive"))
      (node (ref "SD1") (pin "9") (pinfunction "9_9") (pintype "bidirectional"))
    )
    (net (code "21") (name "Net-(T1-D)") (class "Default")
      (node (ref "R5") (pin "1") (pinfunction "1_1") (pintype "passive"))
      (node (ref "T1") (pin "1") (pinfunction "D_1") (pintype "passive"))
      (node (ref "T3") (pin "1") (pinfunction "D_1") (pintype "passive"))
    )
    (net (code "22") (name "Net-(T1-G)") (class "Default")
      (node (ref "R1") (pin "2") (pinfunction "2_2") (pintype "passive"))
      (node (ref "R2") (pin "2") (pinfunction "2_2") (pintype "passive"))
      (node (ref "T1") (pin "3") (pinfunction "G_3") (pintype "passive"))
    )
    (net (code "23") (name "Net-(T2-G)") (class "Default")
      (node (ref "R4") (pin "1") (pinfunction "1_1") (pintype "passive"))
      (node (ref "R5") (pin "2") (pinfunction "2_2") (pintype "passive"))
      (node (ref "T2") (pin "3") (pinfunction "G_3") (pintype "passive"))
    )
    (net (code "24") (name "Net-(T3-G)") (class "Default")
      (node (ref "R11") (pin "2") (pinfunction "2_2") (pintype "passive"))
      (node (ref "R7") (pin "2") (pinfunction "2_2") (pintype "passive"))
      (node (ref "T3") (pin "3") (pinfunction "G_3") (pintype "passive"))
    )
    (net (code "25") (name "Net-(T4-D)") (class "Default")
      (node (ref "R29") (pin "1") (pinfunction "1_1") (pintype "passive"))
      (node (ref "T4") (pin "1") (pinfunction "D_1") (pintype "passive"))
    )
    (net (code "26") (name "Net-(T4-G)") (class "Default")
      (node (ref "R24") (pin "1") (pinfunction "1_1") (pintype "passive"))
      (node (ref "R26") (pin "2") (pinfunction "2_2") (pintype "passive"))
      (node (ref "T4") (pin "3") (pinfunction "G_3") (pintype "passive"))
    )
    (net (code "27") (name "Net-(T5-G)") (class "Default")
      (node (ref "R25") (pin "1") (pinfunction "1_1") (pintype "passive"))
      (node (ref "R29") (pin "2") (pinfunction "2_2") (pintype "passive"))
      (node (ref "T5") (pin "3") (pinfunction "G_3") (pintype "passive"))
    )
    (net (code "28") (name "Net-(T6-D)") (class "Default")
      (node (ref "R39") (pin "1") (pinfunction "1_1") (pintype "passive"))
      (node (ref "T6") (pin "1") (pinfunction "D_1") (pintype "passive"))
    )
    (net (code "29") (name "Net-(T6-G)") (class "Default")
      (node (ref "R36") (pin "1") (pinfunction "1_1") (pintype "passive"))
      (node (ref "R38") (pin "2") (pinfunction "2_2") (pintype "passive"))
      (node (ref "T6") (pin "3") (pinfunction "G_3") (pintype "passive"))
    )
    (net (code "30") (name "Net-(T7-G)") (class "Default")
      (node (ref "R37") (pin "1") (pinfunction "1_1") (pintype "passive"))
      (node (ref "R39") (pin "2") (pinfunction "2_2") (pintype "passive"))
      (node (ref "T7") (pin "3") (pinfunction "G_3") (pintype "passive"))
    )
    (net (code "31") (name "Net-(T8-D)") (class "Default")
      (node (ref "R44") (pin "1") (pinfunction "1_1") (pintype "passive"))
      (node (ref "T8") (pin "1") (pinfunction "D_1") (pintype "passive"))
    )
    (net (code "32") (name "Net-(T8-G)") (class "Default")
      (node (ref "R41") (pin "1") (pinfunction "1_1") (pintype "passive"))
      (node (ref "R43") (pin "2") (pinfunction "2_2") (pintype "passive"))
      (node (ref "T8") (pin "3") (pinfunction "G_3") (pintype "passive"))
    )
    (net (code "33") (name "Net-(T9-G)") (class "Default")
      (node (ref "R42") (pin "1") (pinfunction "1_1") (pintype "passive"))
      (node (ref "R44") (pin "2") (pinfunction "2_2") (pintype "passive"))
      (node (ref "T9") (pin "3") (pinfunction "G_3") (pintype "passive"))
    )
    (net (code "34") (name "Net-(T10-D)") (class "Default")
      (node (ref "R49") (pin "1") (pinfunction "1_1") (pintype "passive"))
      (node (ref "T10") (pin "1") (pinfunction "D_1") (pintype "passive"))
    )
    (net (code "35") (name "Net-(T10-G)") (class "Default")
      (node (ref "R46") (pin "1") (pinfunction "1_1") (pintype "passive"))
      (node (ref "R48") (pin "2") (pinfunction "2_2") (pintype "passive"))
      (node (ref "T10") (pin "3") (pinfunction "G_3") (pintype "passive"))
    )
    (net (code "36") (name "Net-(T11-G)") (class "Default")
      (node (ref "R47") (pin "1") (pinfunction "1_1") (pintype "passive"))
      (node (ref "R49") (pin "2") (pinfunction "2_2") (pintype "passive"))
      (node (ref "T11") (pin "3") (pinfunction "G_3") (pintype "passive"))
    )
    (net (code "37") (name "Net-(T12-D)") (class "Default")
      (node (ref "R54") (pin "1") (pinfunction "1_1") (pintype "passive"))
      (node (ref "T12") (pin "1") (pinfunction "D_1") (pintype "passive"))
    )
    (net (code "38") (name "Net-(T12-G)") (class "Default")
      (node (ref "R51") (pin "1") (pinfunction "1_1") (pintype "passive"))
      (node (ref "R53") (pin "2") (pinfunction "2_2") (pintype "passive"))
      (node (ref "T12") (pin "3") (pinfunction "G_3") (pintype "passive"))
    )
    (net (code "39") (name "Net-(T13-G)") (class "Default")
      (node (ref "R52") (pin "1") (pinfunction "1_1") (pintype "passive"))
      (node (ref "R54") (pin "2") (pinfunction "2_2") (pintype "passive"))
      (node (ref "T13") (pin "3") (pinfunction "G_3") (pintype "passive"))
    )
    (net (code "40") (name "Net-(X1B-1)") (class "Default")
      (node (ref "Q1") (pin "10") (pinfunction "D_10") (pintype "passive"))
      (node (ref "Q1") (pin "11") (pinfunction "D_11") (pintype "passive"))
      (node (ref "Q1") (pin "5") (pinfunction "D_5") (pintype "passive"))
      (node (ref "Q1") (pin "6") (pinfunction "D_6") (pintype "passive"))
      (node (ref "Q1") (pin "7") (pinfunction "D_7") (pintype "passive"))
      (node (ref "Q1") (pin "8") (pinfunction "D_8") (pintype "passive"))
      (node (ref "Q1") (pin "9") (pinfunction "D_9") (pintype "passive"))
      (node (ref "X1") (pin "2") (pinfunction "1_2") (pintype "passive"))
    )
    (net (code "41") (name "PA0_SENSOR_I2C_SDA") (class "Default")
      (node (ref "IC2") (pin "1") (pinfunction "PA0/I2C0_SDA#0/TIM0_CC0#0,1_1") (pintype "bidirectional"))
      (node (ref "R56") (pin "2") (pinfunction "2_2") (pintype "passive"))
      (node (ref "X4") (pin "1") (pinfunction "1_1") (pintype "passive"))
    )
    (net (code "42") (name "PA1_SENSOR_I2C_SCL") (class "Default")
      (node (ref "IC2") (pin "2") (pinfunction "PA1/CMU_CLK1#0/I2C0_SCL#0/TIM0_CC1#0,1_2") (pintype "bidirectional"))
      (node (ref "R58") (pin "1") (pinfunction "1_1") (pintype "passive"))
      (node (ref "X4") (pin "4") (pinfunction "1_4") (pintype "passive"))
    )
    (net (code "43") (name "PA2_POWER_LED") (class "Default")
      (node (ref "IC2") (pin "3") (pinfunction "PA2/CMU_CLK0#0/TIM0_CC2#0,1_3") (pintype "bidirectional"))
      (node (ref "R18") (pin "1") (pinfunction "1_1") (pintype "passive"))
    )
    (net (code "44") (name "PA3_KEY_START_STOP") (class "Default")
      (node (ref "C24") (pin "2") (pinfunction "2_2") (pintype "passive"))
      (node (ref "IC2") (pin "4") (pinfunction "PA3/TIM0_CDTI0#0_4") (pintype "bidirectional"))
      (node (ref "LSP2") (pin "MP") (pinfunction "MP_MP") (pintype "passive"))
      (node (ref "R20") (pin "1") (pinfunction "1_1") (pintype "passive"))
      (node (ref "SW2") (pin "P") (pinfunction "P_P") (pintype "passive"))
      (node (ref "SW2") (pin "P1") (pinfunction "P1_P1") (pintype "passive"))
    )
    (net (code "45") (name "PA4_SIGNAL_POWER") (class "Default")
      (node (ref "IC2") (pin "5") (pinfunction "PA4/TIM0_CDTI1#0_5") (pintype "bidirectional"))
      (node (ref "LSP1") (pin "MP") (pinfunction "MP_MP") (pintype "passive"))
      (node (ref "R19") (pin "2") (pinfunction "2_2") (pintype "passive"))
      (node (ref "R7") (pin "1") (pinfunction "1_1") (pintype "passive"))
      (node (ref "SW1") (pin "P") (pinfunction "P_P") (pintype "passive"))
      (node (ref "SW1") (pin "P1") (pinfunction "P1_P1") (pintype "passive"))
    )
    (net (code "46") (name "PA5_LOG_FLUSH_LED") (class "Default")
      (node (ref "IC2") (pin "6") (pinfunction "PA5/LEU1_TX#1/TIM0_CDTI2#0_6") (pintype "bidirectional"))
      (node (ref "R21") (pin "1") (pinfunction "1_1") (pintype "passive"))
    )
    (net (code "47") (name "PB7_LFXTAL_P") (class "Default")
      (node (ref "C15") (pin "2") (pinfunction "2_2") (pintype "passive"))
      (node (ref "IC2") (pin "15") (pinfunction "PB7/LFXTAL_P/US1_CLK#0_15") (pintype "bidirectional"))
      (node (ref "Q3") (pin "2") (pinfunction "2_2") (pintype "passive"))
    )
    (net (code "48") (name "PB8_LFXTAL_N") (class "Default")
      (node (ref "C10") (pin "2") (pinfunction "2_2") (pintype "passive"))
      (node (ref "IC2") (pin "16") (pinfunction "PB8/LFXTAL_N/US1_CS#0_16") (pintype "bidirectional"))
      (node (ref "Q3") (pin "1") (pinfunction "1_1") (pintype "passive"))
    )
    (net (code "49") (name "PB11_POWER_GOOD") (class "Default")
      (node (ref "IC1") (pin "8") (pinfunction "PG_8") (pintype "output"))
      (node (ref "IC2") (pin "21") (pinfunction "PB11/DAC0_OUT0/OPAMP_OUT0/LETIM0_OUT0#1_21") (pintype "bidirectional"))
      (node (ref "R12") (pin "2") (pinfunction "2_2") (pintype "passive"))
    )
    (net (code "50") (name "PB13_HFXTAL_P") (class "Default")
      (node (ref "C14") (pin "2") (pinfunction "2_2") (pintype "passive"))
      (node (ref "IC2") (pin "24") (pinfunction "PB13/HFXTAL_P/LEU0_TX#1_24") (pintype "bidirectional"))
      (node (ref "Q2") (pin "2") (pinfunction "2_2") (pintype "passive"))
    )
    (net (code "51") (name "PB14_HFXTAL_N") (class "Default")
      (node (ref "C9") (pin "2") (pinfunction "2_2") (pintype "passive"))
      (node (ref "IC2") (pin "25") (pinfunction "PB14/HFXTAL_N/LEU0_RX#1_25") (pintype "bidirectional"))
      (node (ref "Q2") (pin "1") (pinfunction "1_1") (pintype "passive"))
    )
    (net (code "52") (name "PC0_US1_TX") (class "Default")
      (node (ref "IC2") (pin "9") (pinfunction "PC0/ACMP0_CH0/PCNT0_S0IN#2/US1_TX#0_9") (pintype "bidirectional"))
      (node (ref "X7") (pin "1") (pinfunction "1_1") (pintype "passive"))
    )
    (net (code "53") (name "PC1_US1_RX") (class "Default")
      (node (ref "IC2") (pin "10") (pinfunction "PC1/ACMP0_CH1/PCNT0_S1IN#2/US1_RX#0_10") (pintype "bidirectional"))
      (node (ref "X7") (pin "2") (pinfunction "1_2") (pintype "passive"))
    )
    (net (code "54") (name "PC2_SD_SDO") (class "Default")
      (node (ref "IC2") (pin "11") (pinfunction "PC2/ACMP0_CH2/US2_TX_11") (pintype "bidirectional"))
      (node (ref "SD1") (pin "2") (pinfunction "2_2") (pintype "bidirectional"))
    )
    (net (code "55") (name "PC3_SD_SDI") (class "Default")
      (node (ref "IC2") (pin "12") (pinfunction "PC3/ACMP0_CH3/US2_RX_12") (pintype "bidirectional"))
      (node (ref "R34") (pin "1") (pinfunction "1_1") (pintype "passive"))
      (node (ref "SD1") (pin "7") (pinfunction "7_7") (pintype "bidirectional"))
    )
    (net (code "56") (name "PC4_SD_CLK") (class "Default")
      (node (ref "IC2") (pin "13") (pinfunction "PC4/ACMP0_CH4/LETIM0_OUT0#3/PCNT1_S0IN/US2_CLK_13") (pintype "bidirectional"))
      (node (ref "SD1") (pin "5") (pinfunction "5_5") (pintype "bidirectional"))
    )
    (net (code "57") (name "PC5_SD_CS") (class "Default")
      (node (ref "IC2") (pin "14") (pinfunction "PC5/ACMP0_CH5/LETIM0_OUT1#3/PCNT1_S1IN/US2_CS_14") (pintype "bidirectional"))
      (node (ref "SD1") (pin "1") (pinfunction "1_1") (pintype "bidirectional"))
    )
    (net (code "58") (name "PC6_SD_CD") (class "Default")
      (node (ref "IC2") (pin "37") (pinfunction "PC6/ACMP0_CH6/I2C0_SDA#2/LEU1_TX#0_37") (pintype "bidirectional"))
      (node (ref "R33") (pin "1") (pinfunction "1_1") (pintype "passive"))
      (node (ref "SD1") (pin "CDS") (pinfunction "CDS_CDS") (pintype "passive"))
    )
    (net (code "59") (name "PC7_SD_WP") (class "Default")
      (node (ref "IC2") (pin "38") (pinfunction "PC7/ACMP0_CH7/I2C0_SCL#2/LEU1_RX#0_38") (pintype "bidirectional"))
      (node (ref "R35") (pin "1") (pinfunction "1_1") (pintype "passive"))
      (node (ref "SD1") (pin "WPS") (pinfunction "WPS_WPS") (pintype "passive"))
    )
    (net (code "60") (name "PC9_SENSOR2_MOSFET") (class "Default")
      (node (ref "IC2") (pin "42") (pinfunction "PC9/ACMP1_CH1/TIM2_CC1#2/US0_CLK#2_42") (pintype "bidirectional"))
      (node (ref "R41") (pin "2") (pinfunction "2_2") (pintype "passive"))
    )
    (net (code "61") (name "PC10_SENSOR2_ADDR") (class "Default")
      (node (ref "IC2") (pin "43") (pinfunction "PC10/ACMP1_CH2/TIM2_CC2#2/US0_RX#2_43") (pintype "bidirectional"))
      (node (ref "X5") (pin "2") (pinfunction "1_2") (pintype "passive"))
    )
    (net (code "62") (name "PC11_SENSOR2_ALERT") (class "Default")
      (node (ref "IC2") (pin "44") (pinfunction "PC11/ACMP1_CH3/US0_TX#2_44") (pintype "bidirectional"))
      (node (ref "X5") (pin "3") (pinfunction "1_3") (pintype "passive"))
    )
    (net (code "63") (name "PC12_SD_PULLUP") (class "Default")
      (node (ref "IC2") (pin "45") (pinfunction "PC12/ACMP1_CH4/CMU_CLK0#1_45") (pintype "bidirectional"))
      (node (ref "R33") (pin "2") (pinfunction "2_2") (pintype "passive"))
    )
    (net (code "64") (name "PC13_SENSOR2_RESET") (class "Default")
      (node (ref "IC2") (pin "46") (pinfunction "PC13/ACMP1_CH5/PCNT0_S0IN#0/TIM0_CDTI0#1,3/TIM1_CC0#0_46") (pintype "bidirectional"))
      (node (ref "X5") (pin "6") (pinfunction "1_6") (pintype "passive"))
    )
    (net (code "65") (name "PC14_SENSOR2_RESERVE") (class "Default")
      (node (ref "IC2") (pin "47") (pinfunction "PC14/ACMP1_CH6/PCNT0_S1IN#0/TIM0_CDTI1#1,3/TIM1_CC1#0_47") (pintype "bidirectional"))
      (node (ref "X5") (pin "7") (pinfunction "1_7") (pintype "passive"))
    )
    (net (code "66") (name "PD0_SD_POWER") (class "Default")
      (node (ref "IC2") (pin "28") (pinfunction "PD0/ADC0_CH0/PCNT2_S0IN#0/US1_TX#1_28") (pintype "bidirectional"))
      (node (ref "R24") (pin "2") (pinfunction "2_2") (pintype "passive"))
    )
    (net (code "67") (name "PD1_HOLD_POWER") (class "Default")
      (node (ref "IC2") (pin "29") (pinfunction "PD1/ADC0_CH1/PCNT2_S1IN#0/TIM0_CC0#3/US1_RX#1_29") (pintype "bidirectional"))
      (node (ref "R1") (pin "1") (pinfunction "1_1") (pintype "passive"))
    )
    (net (code "68") (name "PD2_PULS1_COUNTER") (class "Default")
      (node (ref "C29") (pin "1") (pinfunction "1_1") (pintype "passive"))
      (node (ref "IC2") (pin "30") (pinfunction "PD2/ADC0_CH2/TIM0_CC1#3/US1_CLK#1_30") (pintype "bidirectional"))
      (node (ref "R50") (pin "2") (pinfunction "2_2") (pintype "passive"))
      (node (ref "T11") (pin "1") (pinfunction "D_1") (pintype "passive"))
    )
    (net (code "69") (name "PD3_PULS2_COUNTER") (class "Default")
      (node (ref "C30") (pin "1") (pinfunction "1_1") (pintype "passive"))
      (node (ref "IC2") (pin "31") (pinfunction "PD3/ADC0_CH3/TIM0_CC2#3/US1_CS#1_31") (pintype "bidirectional"))
      (node (ref "R55") (pin "2") (pinfunction "2_2") (pintype "passive"))
      (node (ref "T13") (pin "1") (pinfunction "D_1") (pintype "passive"))
    )
    (net (code "70") (name "PD4_LEUART_TX") (class "Default")
      (node (ref "IC2") (pin "32") (pinfunction "PD4/ADC0_CH4/LEU0_TX#0_32") (pintype "bidirectional"))
      (node (ref "R28") (pin "1") (pinfunction "1_1") (pintype "passive"))
    )
    (net (code "71") (name "PD5_LEUART_RX") (class "Default")
      (node (ref "IC2") (pin "33") (pinfunction "PD5/ADC0_CH5/LEU0_RX#0_33") (pintype "bidirectional"))
      (node (ref "R27") (pin "1") (pinfunction "1_1") (pintype "passive"))
    )
    (net (code "72") (name "PD6_SENSOR_I2C_SDA") (class "Default")
      (node (ref "IC2") (pin "34") (pinfunction "PD6/ADC0_CH6/I2C0_SDA#1/LETIM0_OUT0#0_34") (pintype "bidirectional"))
      (node (ref "R57") (pin "1") (pinfunction "1_1") (pintype "passive"))
      (node (ref "X5") (pin "1") (pinfunction "1_1") (pintype "passive"))
    )
    (net (code "73") (name "PD7_SENSOR_I2C_SCL") (class "Default")
      (node (ref "IC2") (pin "35") (pinfunction "PD7/ADC0_CH7/I2C0_SCL#1/LETIM0_OUT1#0_35") (pintype "bidirectional"))
      (node (ref "R59") (pin "1") (pinfunction "1_1") (pintype "passive"))
      (node (ref "X5") (pin "4") (pinfunction "1_4") (pintype "passive"))
    )
    (net (code "74") (name "PE9_SENSOR1_MOSFET") (class "Default")
      (node (ref "IC2") (pin "57") (pinfunction "PE9/PCNT2_S1IN#1_57") (pintype "bidirectional"))
      (node (ref "R36") (pin "2") (pinfunction "2_2") (pintype "passive"))
    )
    (net (code "75") (name "PE10_US0_TX") (class "Default")
      (node (ref "IC2") (pin "58") (pinfunction "PE10/TIM1_CC0#1/US0_TX#0_58") (pintype "bidirectional"))
      (node (ref "X3") (pin "1") (pinfunction "1_1") (pintype "passive"))
    )
    (net (code "76") (name "PE11_US0_RX") (class "Default")
      (node (ref "IC2") (pin "59") (pinfunction "PE11/TIM1_CC1#1/US0_RX#0_59") (pintype "bidirectional"))
      (node (ref "X3") (pin "2") (pinfunction "1_2") (pintype "passive"))
    )
    (net (code "77") (name "PE12_SENSOR1_ADDR") (class "Default")
      (node (ref "IC2") (pin "60") (pinfunction "PE12/TIM1_CC2#1/US0_CLK#0_60") (pintype "bidirectional"))
      (node (ref "X4") (pin "2") (pinfunction "1_2") (pintype "passive"))
    )
    (net (code "78") (name "PE13_SENSOR1_ALERT") (class "Default")
      (node (ref "IC2") (pin "61") (pinfunction "PE13/ACMP0_O/US0_CS#0_61") (pintype "bidirectional"))
      (node (ref "X4") (pin "3") (pinfunction "1_3") (pintype "passive"))
    )
    (net (code "79") (name "PE14_SENSOR1_RESET") (class "Default")
      (node (ref "IC2") (pin "62") (pinfunction "PE14/LEU0_TX#2_62") (pintype "bidirectional"))
      (node (ref "X4") (pin "6") (pinfunction "1_6") (pintype "passive"))
    )
    (net (code "80") (name "PE15_SENSOR1_RESERVE") (class "Default")
      (node (ref "IC2") (pin "63") (pinfunction "PE15/LEU0_RX#2_63") (pintype "bidirectional"))
      (node (ref "X4") (pin "7") (pinfunction "1_7") (pintype "passive"))
    )
    (net (code "81") (name "PF0_DBG_SWCLK") (class "Default")
      (node (ref "IC2") (pin "49") (pinfunction "PF0/DBG_SWCLK#0,1/LETIM0_OUT0#2_49") (pintype "bidirectional"))
      (node (ref "X2") (pin "4") (pinfunction "4_4") (pintype "passive"))
    )
    (net (code "82") (name "PF1_DBG_SWDIO") (class "Default")
      (node (ref "IC2") (pin "50") (pinfunction "PF1/DBG_SWDIO#0,1/LETIM0_OUT1#2_50") (pintype "bidirectional"))
      (node (ref "X2") (pin "2") (pinfunction "2_2") (pintype "passive"))
    )
    (net (code "83") (name "PF2_DBG_SWO") (class "Default")
      (node (ref "IC2") (pin "51") (pinfunction "PF2/ACMP1_O/DBG_SWO#0_51") (pintype "bidirectional"))
      (node (ref "X2") (pin "6") (pinfunction "6_6") (pintype "passive"))
    )
    (net (code "84") (name "PULS1_COUNTER") (class "Default")
      (node (ref "R46") (pin "2") (pinfunction "2_2") (pintype "passive"))
      (node (ref "X6") (pin "1") (pinfunction "1_1") (pintype "passive"))
    )
    (net (code "85") (name "PULS2_COUNTER") (class "Default")
      (node (ref "R51") (pin "2") (pinfunction "2_2") (pintype "passive"))
      (node (ref "X6") (pin "3") (pinfunction "1_3") (pintype "passive"))
    )
    (net (code "86") (name "RXD_HOST") (class "Default")
      (node (ref "J1") (pin "P$3") (pinfunction "3-RIGHT_P$3") (pintype "bidirectional"))
      (node (ref "R28") (pin "2") (pinfunction "2_2") (pintype "passive"))
    )
    (net (code "87") (name "SD_3V") (class "Default")
      (node (ref "C25") (pin "1") (pinfunction "1_1") (pintype "passive"))
      (node (ref "C26") (pin "1") (pinfunction "1_1") (pintype "passive"))
      (node (ref "R30") (pin "2") (pinfunction "2_2") (pintype "passive"))
      (node (ref "R31") (pin "2") (pinfunction "2_2") (pintype "passive"))
      (node (ref "R32") (pin "2") (pinfunction "2_2") (pintype "passive"))
      (node (ref "R34") (pin "2") (pinfunction "2_2") (pintype "passive"))
      (node (ref "R35") (pin "2") (pinfunction "2_2") (pintype "passive"))
      (node (ref "SD1") (pin "4") (pinfunction "4_4") (pintype "bidirectional"))
      (node (ref "T5") (pin "1") (pinfunction "D_1") (pintype "passive"))
    )
    (net (code "88") (name "TXD_HOST") (class "Default")
      (node (ref "J1") (pin "P$2") (pinfunction "2-LEFT_P$2") (pintype "bidirectional"))
      (node (ref "R27") (pin "2") (pinfunction "2_2") (pintype "passive"))
    )
    (net (code "89") (name "VBATT") (class "Default")
      (node (ref "C6") (pin "2") (pinfunction "2_2") (pintype "passive"))
      (node (ref "D1") (pin "C") (pinfunction "C_C") (pintype "passive"))
      (node (ref "D3") (pin "1") (pinfunction "C_1") (pintype "passive"))
      (node (ref "R22") (pin "2") (pinfunction "2_2") (pintype "passive"))
      (node (ref "R4") (pin "2") (pinfunction "2_2") (pintype "passive"))
      (node (ref "T2") (pin "2") (pinfunction "S_2") (pintype "passive"))
    )
    (net (code "90") (name "VDD_SENSOR1") (class "Default")
      (node (ref "C27") (pin "1") (pinfunction "1_1") (pintype "passive"))
      (node (ref "R40") (pin "2") (pinfunction "2_2") (pintype "passive"))
      (node (ref "T7") (pin "1") (pinfunction "D_1") (pintype "passive"))
      (node (ref "X4") (pin "5") (pinfunction "1_5") (pintype "passive"))
    )
    (net (code "91") (name "VDD_SENSOR2") (class "Default")
      (node (ref "C28") (pin "1") (pinfunction "1_1") (pintype "passive"))
      (node (ref "R45") (pin "2") (pinfunction "2_2") (pintype "passive"))
      (node (ref "T9") (pin "1") (pinfunction "D_1") (pintype "passive"))
      (node (ref "X5") (pin "5") (pinfunction "1_5") (pintype "passive"))
    )
    (net (code "92") (name "VMCU") (class "Default")
      (node (ref "C11") (pin "2") (pinfunction "2_2") (pintype "passive"))
      (node (ref "C12") (pin "2") (pinfunction "2_2") (pintype "passive"))
      (node (ref "C13") (pin "2") (pinfunction "2_2") (pintype "passive"))
      (node (ref "C17") (pin "2") (pinfunction "2_2") (pintype "passive"))
      (node (ref "C19") (pin "2") (pinfunction "2_2") (pintype "passive"))
      (node (ref "C21") (pin "2") (pinfunction "2_2") (pintype "passive"))
      (node (ref "C22") (pin "2") (pinfunction "2_2") (pintype "passive"))
      (node (ref "D2") (pin "2") (pinfunction "A1_2") (pintype "passive"))
      (node (ref "D2") (pin "3") (pinfunction "A2_3") (pintype "passive"))
      (node (ref "IC2") (pin "26") (pinfunction "IOVDD_3_26") (pintype "power_in"))
      (node (ref "IC2") (pin "39") (pinfunction "VDD_DREG_39") (pintype "power_in"))
      (node (ref "IC2") (pin "55") (pinfunction "IOVDD_5_55") (pintype "power_in"))
      (node (ref "IC2") (pin "8") (pinfunction "IOVDD_0_8") (pintype "power_in"))
      (node (ref "L2") (pin "1") (pinfunction "1_1") (pintype "passive"))
      (node (ref "R16") (pin "2") (pinfunction "2_2") (pintype "passive"))
      (node (ref "R20") (pin "2") (pinfunction "2_2") (pintype "passive"))
      (node (ref "R37") (pin "2") (pinfunction "2_2") (pintype "passive"))
      (node (ref "R42") (pin "2") (pinfunction "2_2") (pintype "passive"))
      (node (ref "R47") (pin "2") (pinfunction "2_2") (pintype "passive"))
      (node (ref "R52") (pin "2") (pinfunction "2_2") (pintype "passive"))
      (node (ref "R56") (pin "1") (pinfunction "1_1") (pintype "passive"))
      (node (ref "R57") (pin "2") (pinfunction "2_2") (pintype "passive"))
      (node (ref "R58") (pin "2") (pinfunction "2_2") (pintype "passive"))
      (node (ref "R59") (pin "2") (pinfunction "2_2") (pintype "passive"))
      (node (ref "R6") (pin "2") (pinfunction "2_2") (pintype "passive"))
      (node (ref "T11") (pin "2") (pinfunction "S_2") (pintype "passive"))
      (node (ref "T13") (pin "2") (pinfunction "S_2") (pintype "passive"))
      (node (ref "T2") (pin "1") (pinfunction "D_1") (pintype "passive"))
      (node (ref "T7") (pin "2") (pinfunction "S_2") (pintype "passive"))
      (node (ref "T9") (pin "2") (pinfunction "S_2") (pintype "passive"))
      (node (ref "X2") (pin "1") (pinfunction "1_1") (pintype "passive"))
    )
    (net (code "93") (name "VSD_CARD") (class "Default")
      (node (ref "C4") (pin "+") (pinfunction "+_+") (pintype "passive"))
      (node (ref "C5") (pin "1") (pinfunction "1_1") (pintype "passive"))
      (node (ref "D2") (pin "1") (pinfunction "C_1") (pintype "passive"))
      (node (ref "R25") (pin "2") (pinfunction "2_2") (pintype "passive"))
      (node (ref "T5") (pin "2") (pinfunction "S_2") (pintype "passive"))
    )
    (net (code "94") (name "unconnected-(BH1-+-Pad+1)") (class "Default")
      (node (ref "BH1") (pin "+1") (pinfunction "+_+1") (pintype "passive"))
    )
    (net (code "95") (name "unconnected-(IC2A-PA6{slash}LEU1_RX#1-Pad7)") (class "Default")
      (node (ref "IC2") (pin "7") (pinfunction "PA6/LEU1_RX#1_7") (pintype "bidirectional"))
    )
    (net (code "96") (name "unconnected-(IC2A-PA8{slash}TIM2_CC0#0-Pad17)") (class "Default")
      (node (ref "IC2") (pin "17") (pinfunction "PA8/TIM2_CC0#0_17") (pintype "bidirectional"))
    )
    (net (code "97") (name "unconnected-(IC2A-PA9{slash}TIM2_CC1#0-Pad18)") (class "Default")
      (node (ref "IC2") (pin "18") (pinfunction "PA9/TIM2_CC1#0_18") (pintype "bidirectional"))
    )
    (net (code "98") (name "unconnected-(IC2A-PA10{slash}TIM2_CC2#0-Pad19)") (class "Default")
      (node (ref "IC2") (pin "19") (pinfunction "PA10/TIM2_CC2#0_19") (pintype "bidirectional"))
    )
    (net (code "99") (name "unconnected-(IC2B-PB12{slash}DAC0_OUT1{slash}OPAMP_OUT1{slash}LETIM0_OUT1#1-Pad22)") (class "Default")
      (node (ref "IC2") (pin "22") (pinfunction "PB12/DAC0_OUT1/OPAMP_OUT1/LETIM0_OUT1#1_22") (pintype "bidirectional"))
    )
    (net (code "100") (name "unconnected-(IC2C-PC8{slash}ACMP1_CH0{slash}TIM2_CC0#2{slash}US0_CS#2-Pad41)") (class "Default")
      (node (ref "IC2") (pin "41") (pinfunction "PC8/ACMP1_CH0/TIM2_CC0#2/US0_CS#2_41") (pintype "bidirectional"))
    )
    (net (code "101") (name "unconnected-(IC2C-PC15{slash}ACMP1_CH7{slash}DBG_SWO#1{slash}TIM0_CDTI2#1,3{slash}TIM1_CC2#0-Pad48)") (class "Default")
      (node (ref "IC2") (pin "48") (pinfunction "PC15/ACMP1_CH7/DBG_SWO#1/TIM0_CDTI2#1,3/TIM1_CC2#0_48") (pintype "bidirectional"))
    )
    (net (code "102") (name "unconnected-(IC2D-PD8{slash}CMU_CLK1#1-Pad36)") (class "Default")
      (node (ref "IC2") (pin "36") (pinfunction "PD8/CMU_CLK1#1_36") (pintype "bidirectional"))
    )
    (net (code "103") (name "unconnected-(IC2E-PE8{slash}PCNT2_S0IN#1-Pad56)") (class "Default")
      (node (ref "IC2") (pin "56") (pinfunction "PE8/PCNT2_S0IN#1_56") (pintype "bidirectional"))
    )
    (net (code "104") (name "unconnected-(IC2F-PF3{slash}TIM0_CDTI0#2-Pad52)") (class "Default")
      (node (ref "IC2") (pin "52") (pinfunction "PF3/TIM0_CDTI0#2_52") (pintype "bidirectional"))
    )
    (net (code "105") (name "unconnected-(IC2F-PF4{slash}TIM0_CDTI1#2-Pad53)") (class "Default")
      (node (ref "IC2") (pin "53") (pinfunction "PF4/TIM0_CDTI1#2_53") (pintype "bidirectional"))
    )
    (net (code "106") (name "unconnected-(IC2F-PF5{slash}TIM0_CDTI2#2-Pad54)") (class "Default")
      (node (ref "IC2") (pin "54") (pinfunction "PF5/TIM0_CDTI2#2_54") (pintype "bidirectional"))
    )
    (net (code "107") (name "unconnected-(SD1-PadG1)") (class "Default")
      (node (ref "SD1") (pin "G1") (pinfunction "G1_G1") (pintype "passive"))
    )
    (net (code "108") (name "unconnected-(SD1-PadG2)") (class "Default")
      (node (ref "SD1") (pin "G2") (pinfunction "G2_G2") (pintype "passive"))
    )
    (net (code "109") (name "unconnected-(SD1-PadG3)") (class "Default")
      (node (ref "SD1") (pin "G3") (pinfunction "G3_G3") (pintype "passive"))
    )
    (net (code "110") (name "unconnected-(SD1-PadG4)") (class "Default")
      (node (ref "SD1") (pin "G4") (pinfunction "G4_G4") (pintype "passive"))
    )
    (net (code "111") (name "unconnected-(X2-Pad7)") (class "Default")
      (node (ref "X2") (pin "7") (pinfunction "7_7") (pintype "passive"))
    )
  )
)
